# shift_clock_v2_0.net
KiCad netlist of a schematic drawn in EAGLE
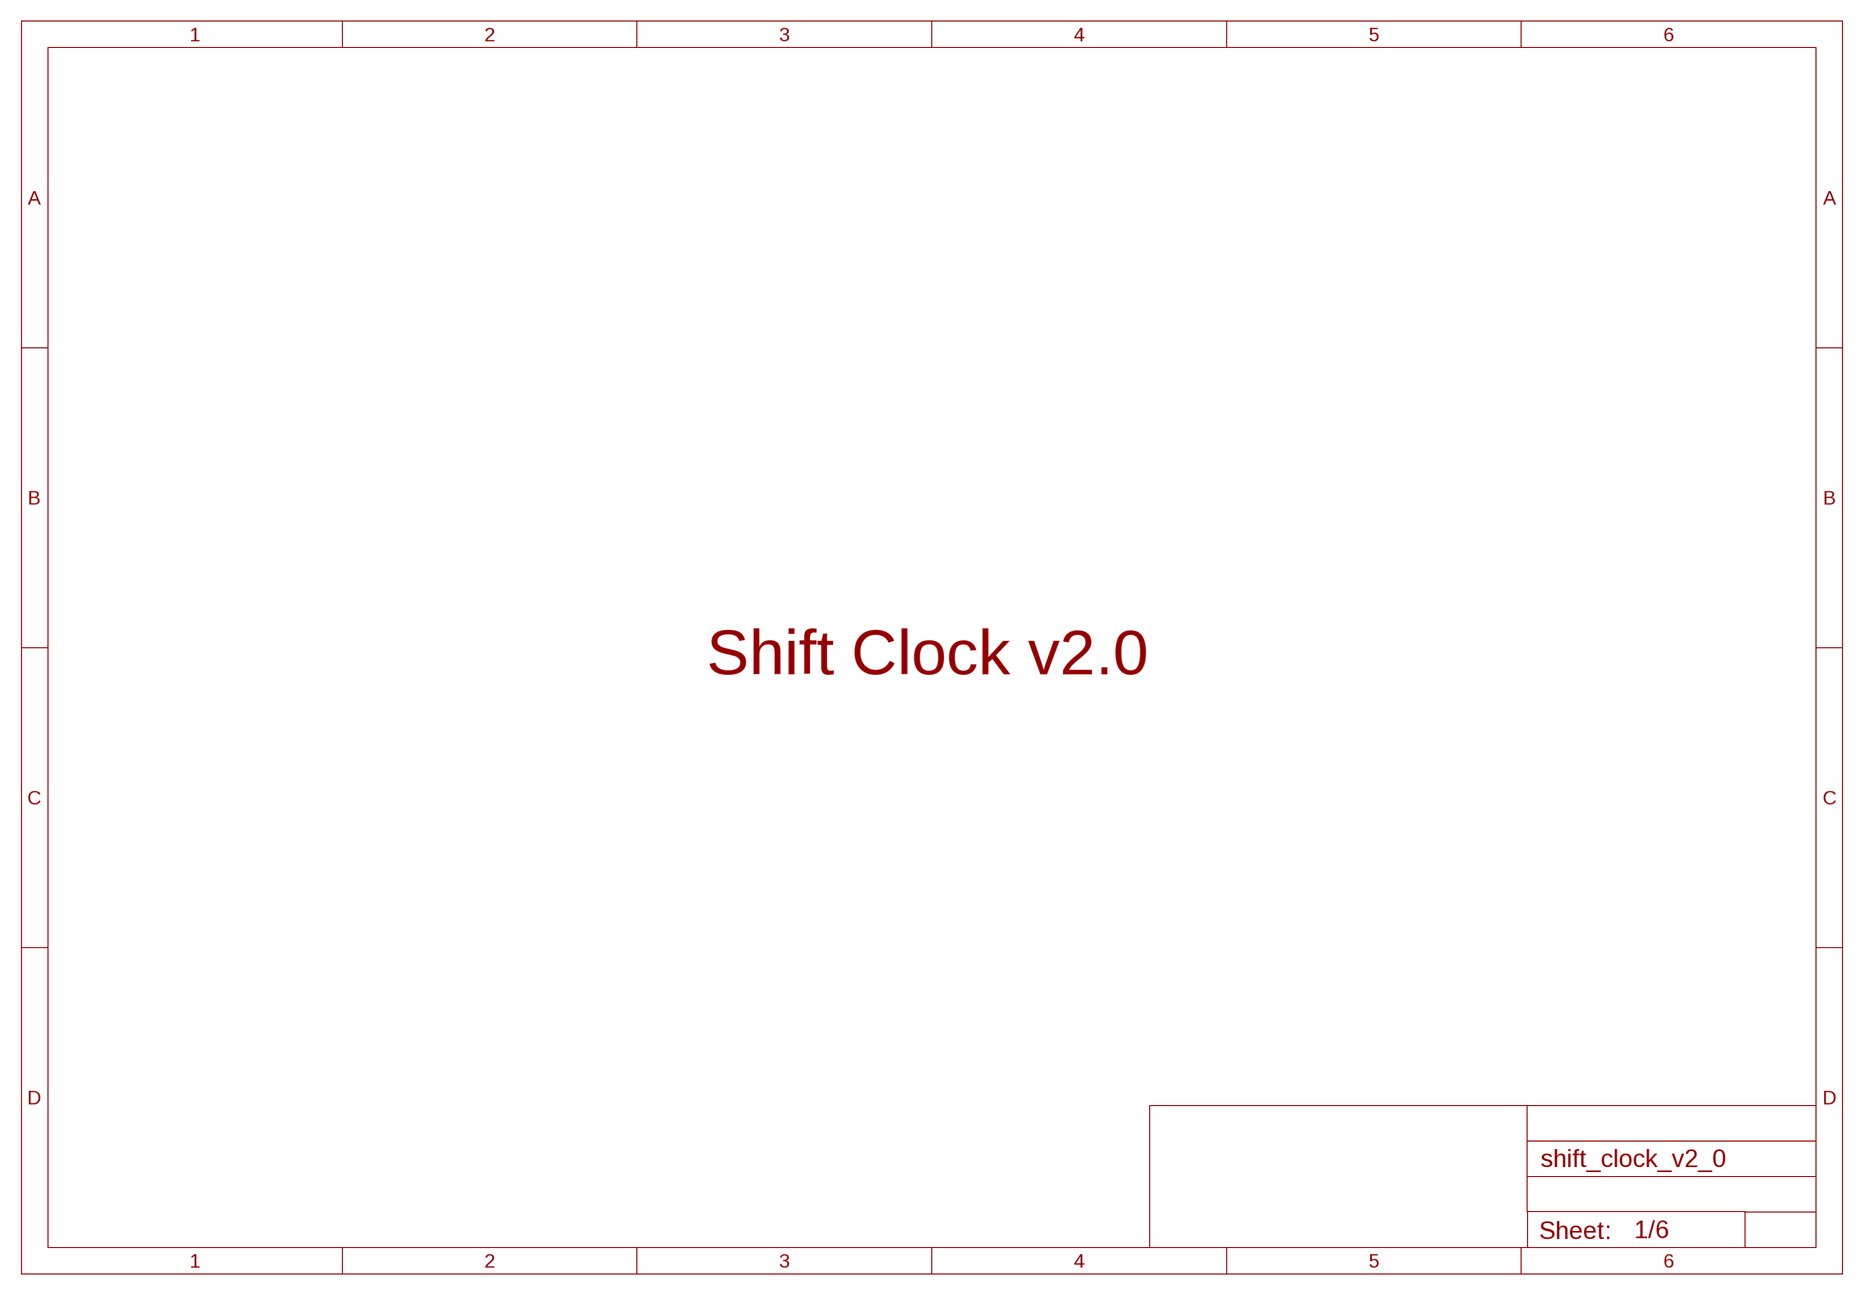
[diagram p0: schematic, sheet 1]
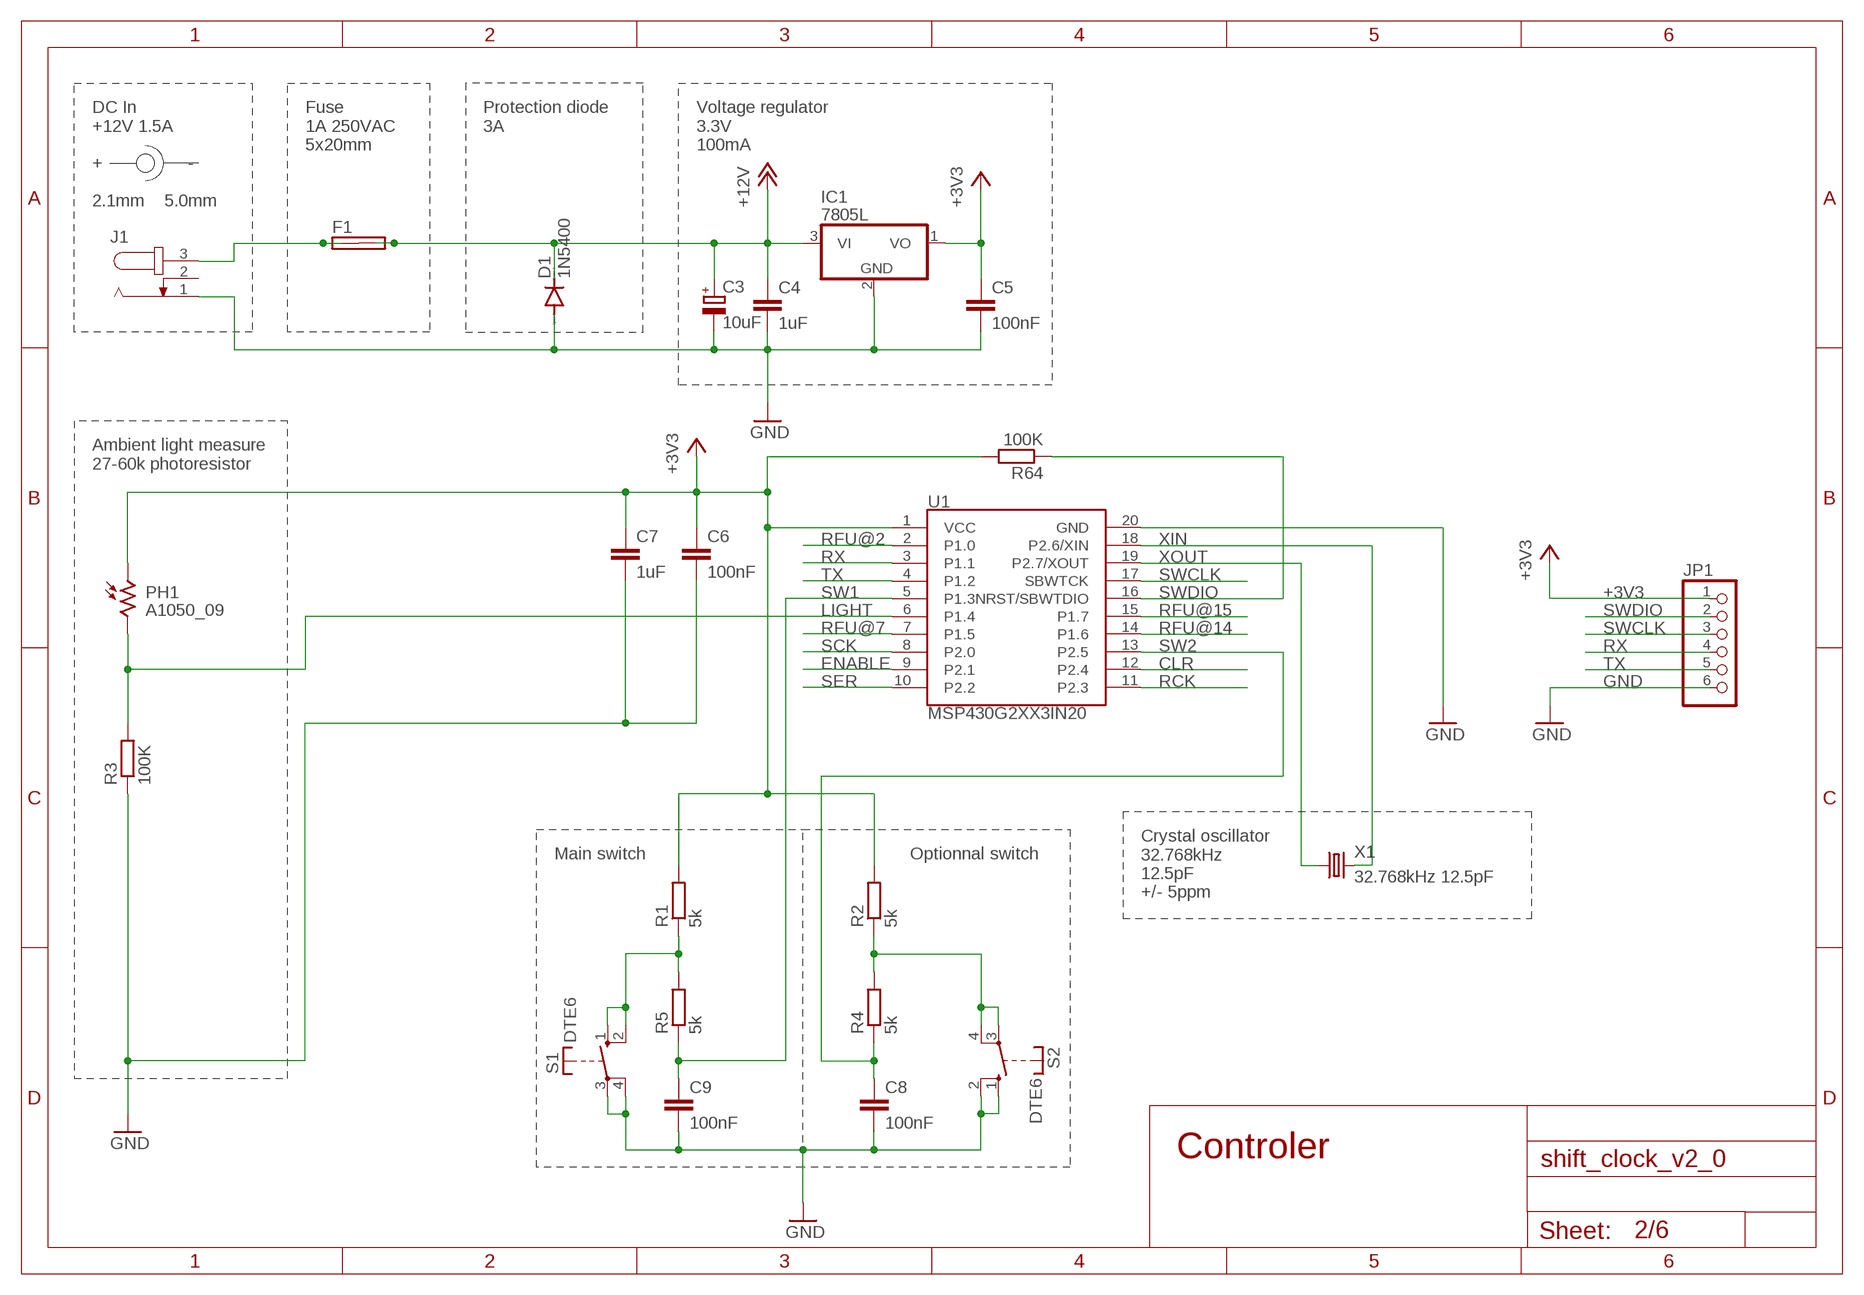
[diagram p1: schematic, sheet 2]
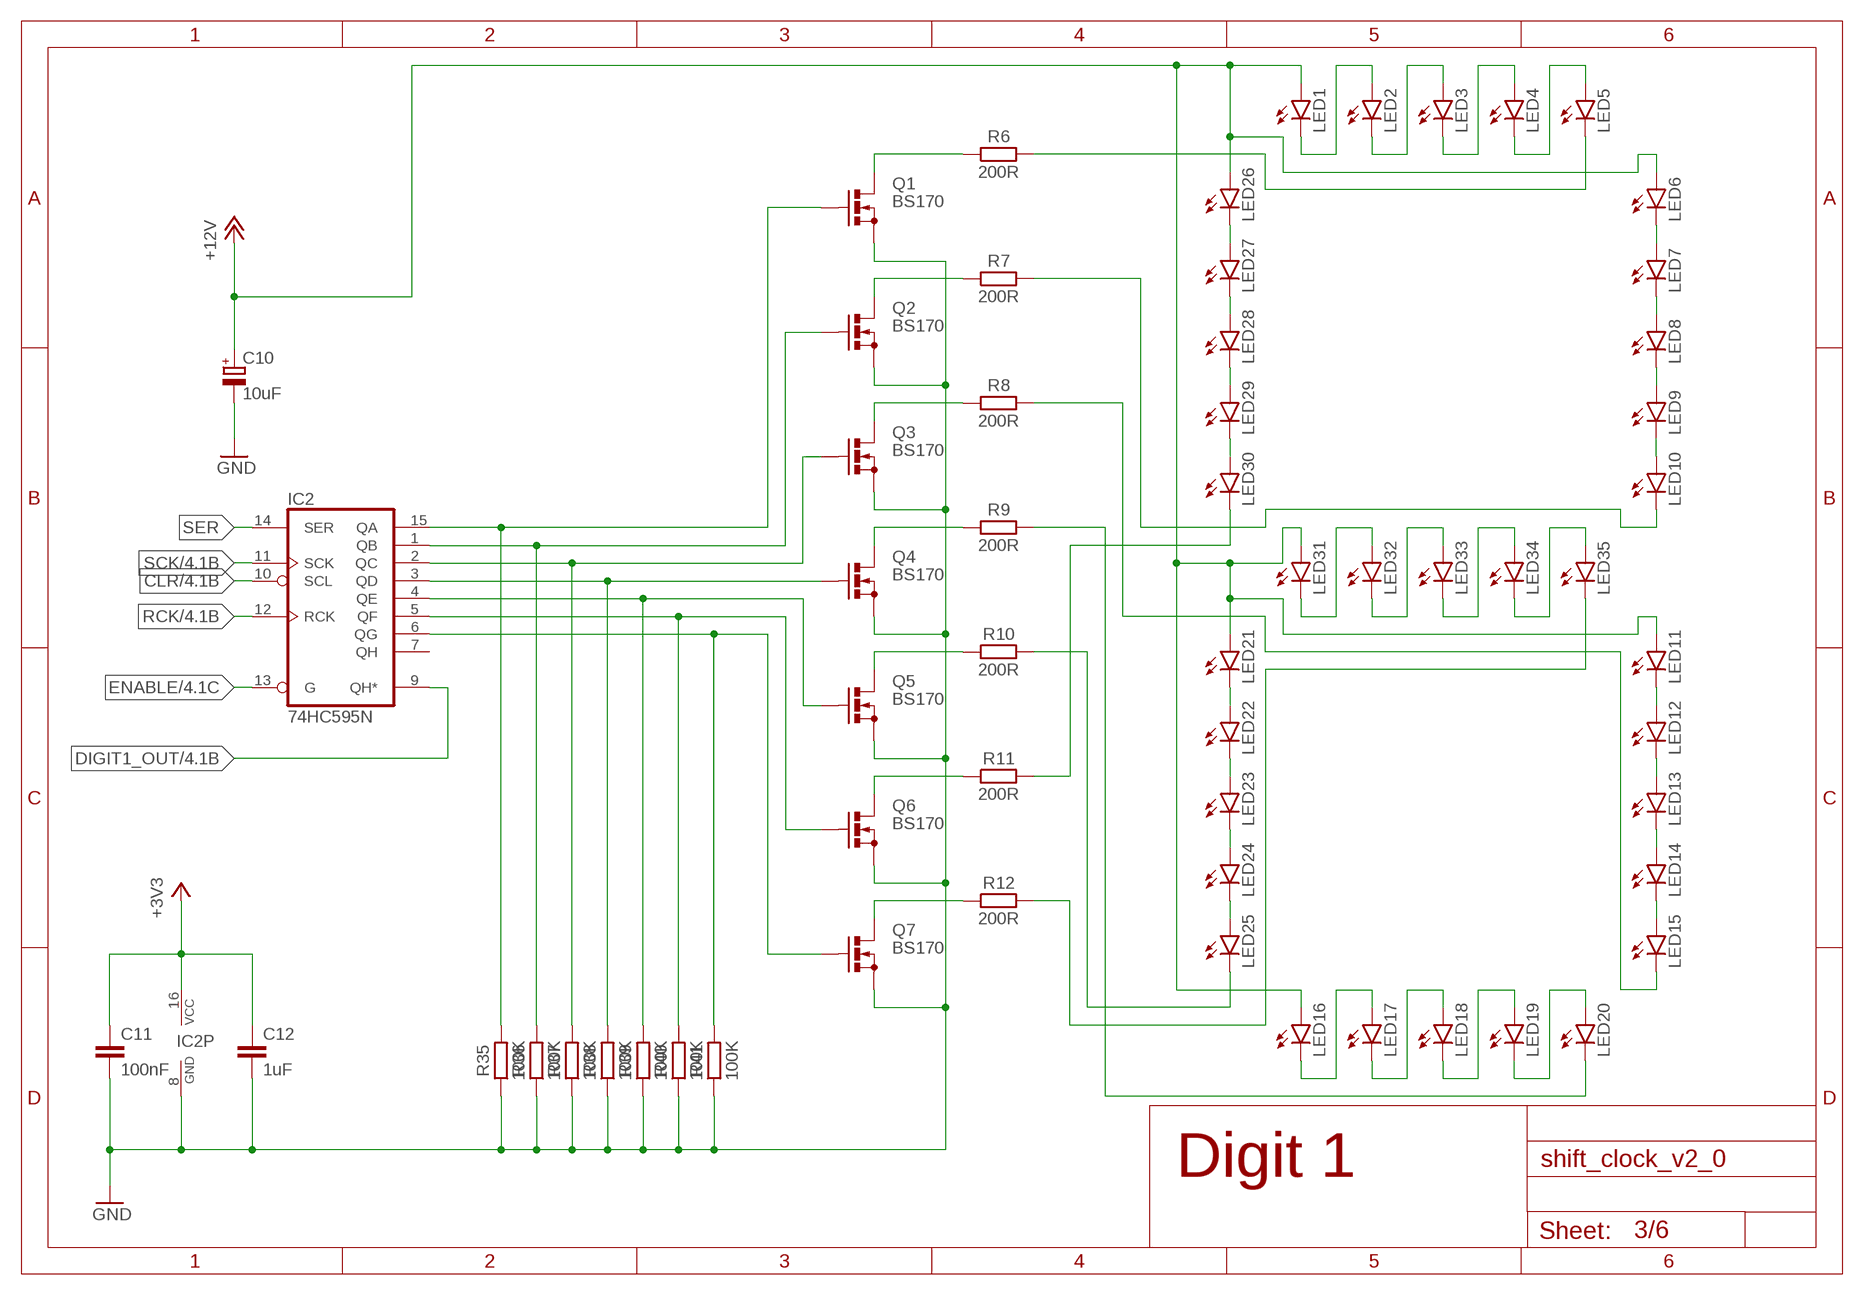
[diagram p2: schematic, sheet 3]
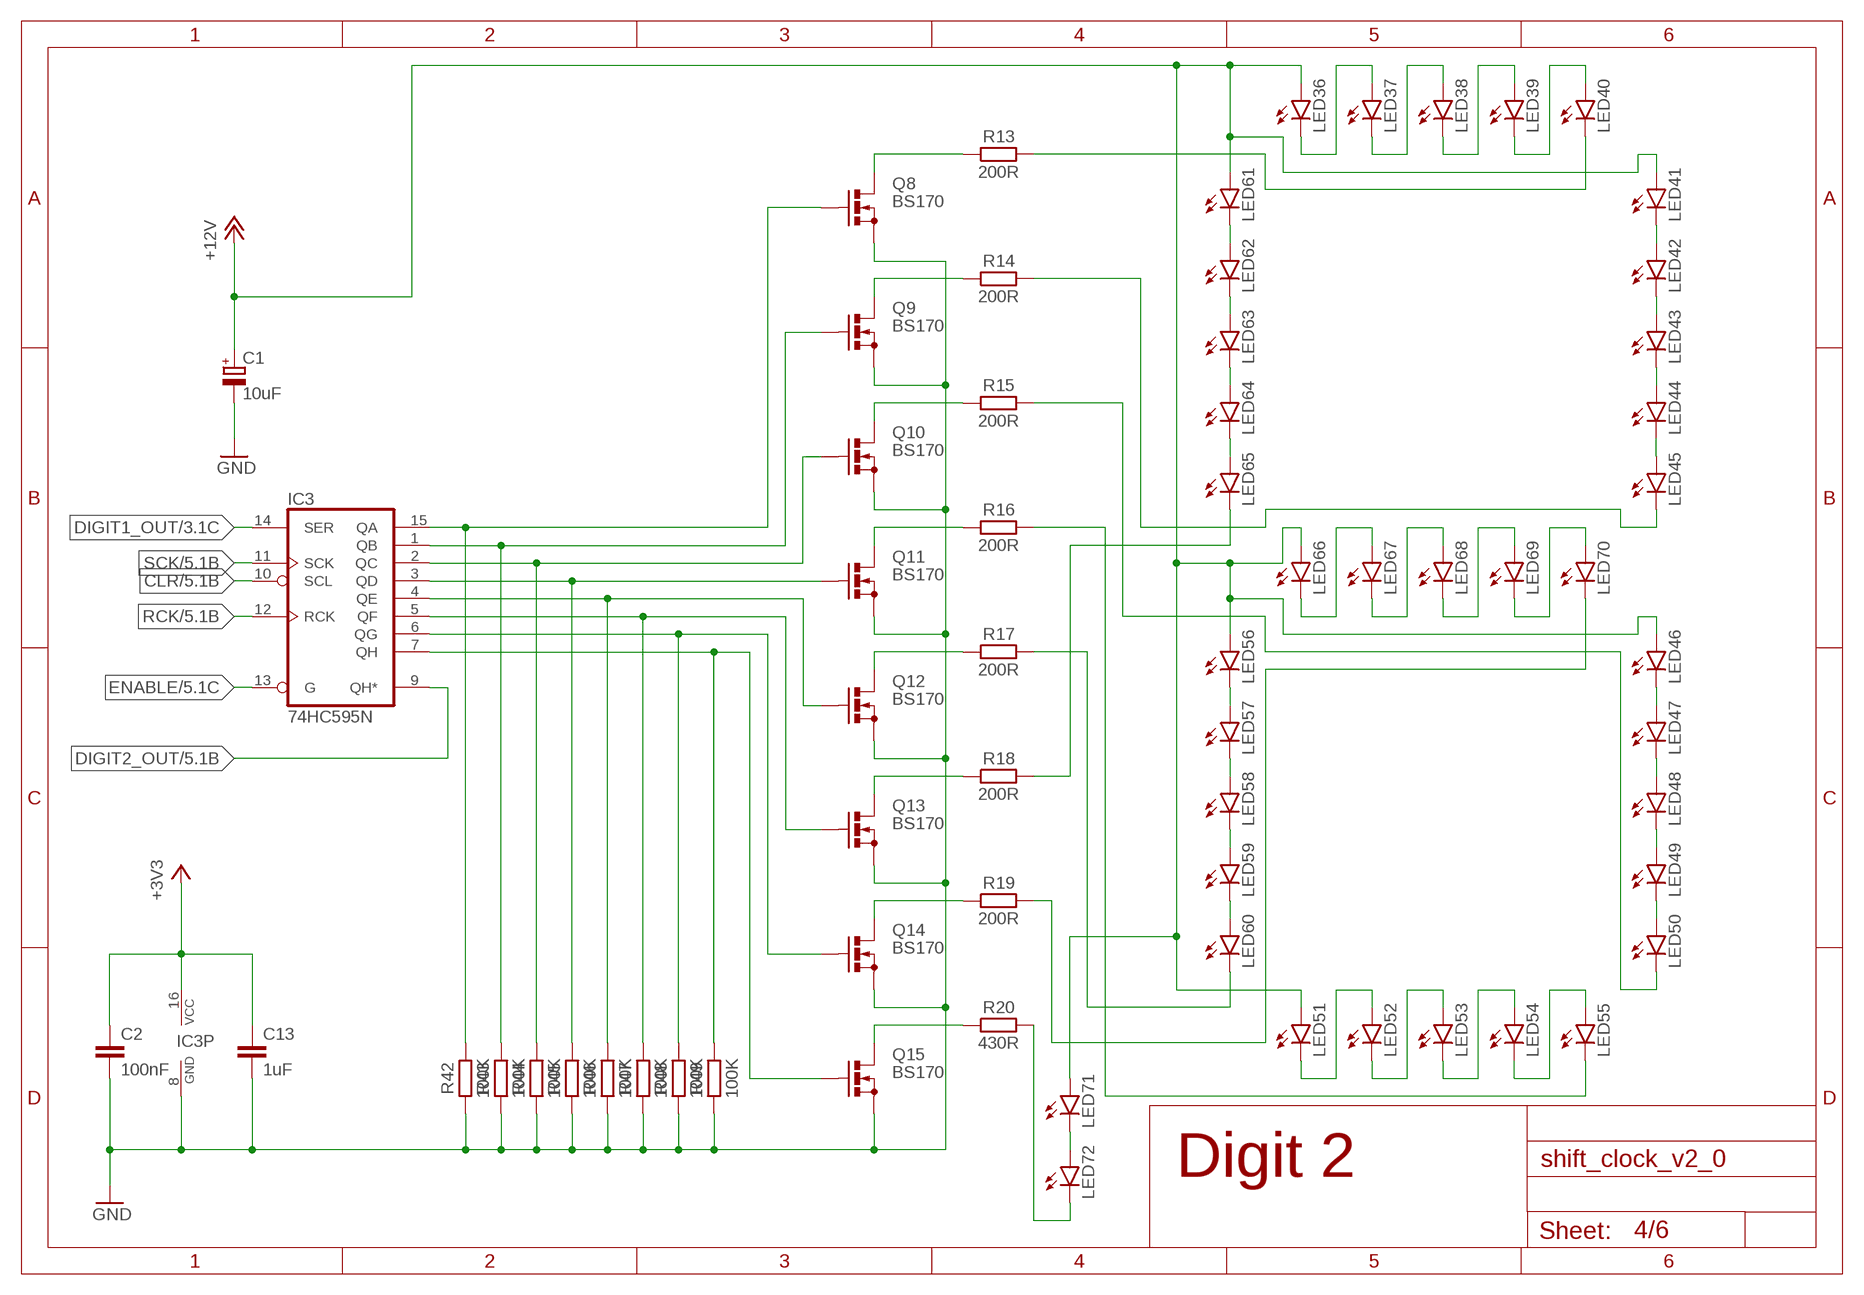
[diagram p3: schematic, sheet 4]
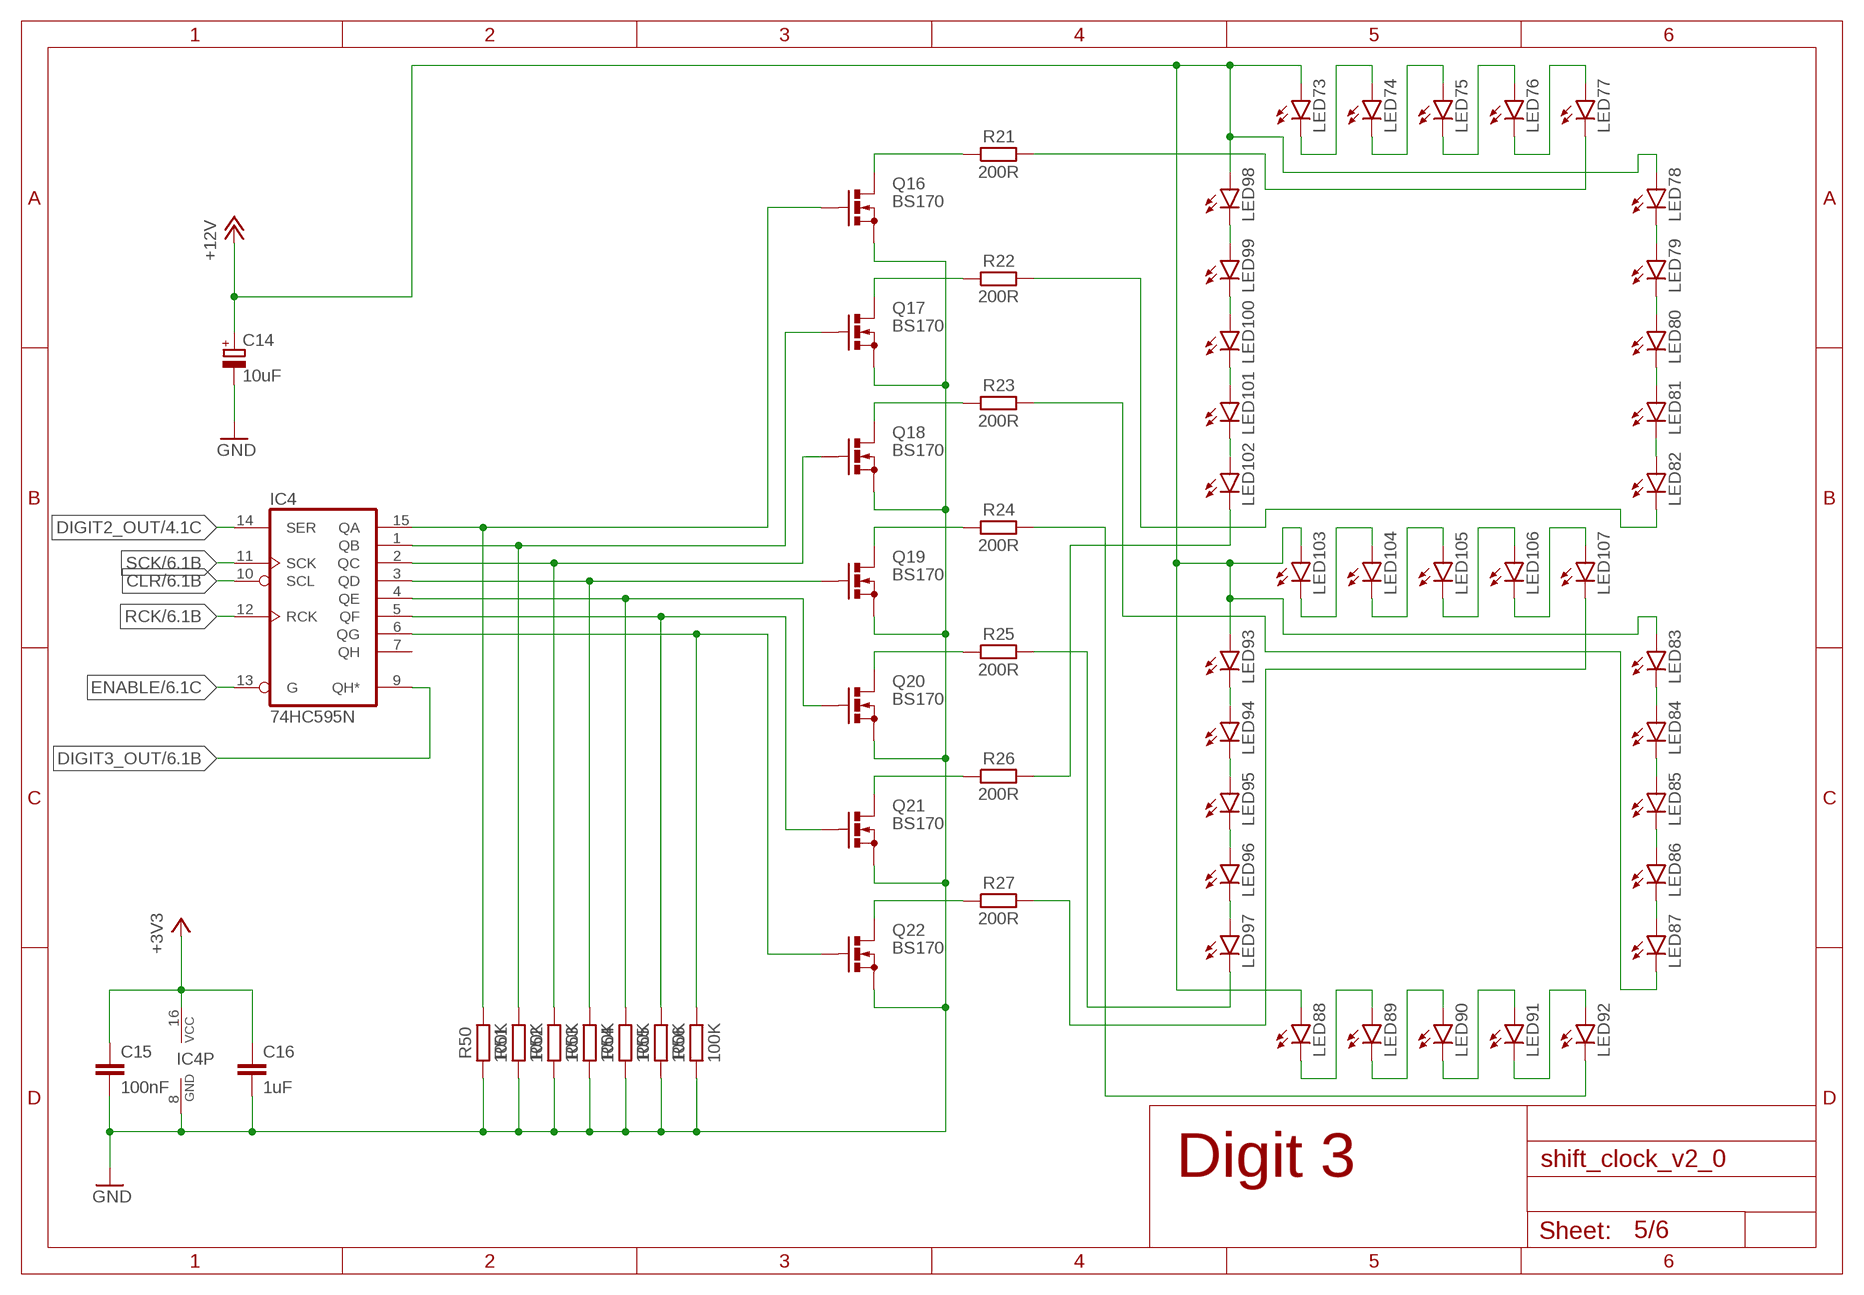
[diagram p4: schematic, sheet 5]
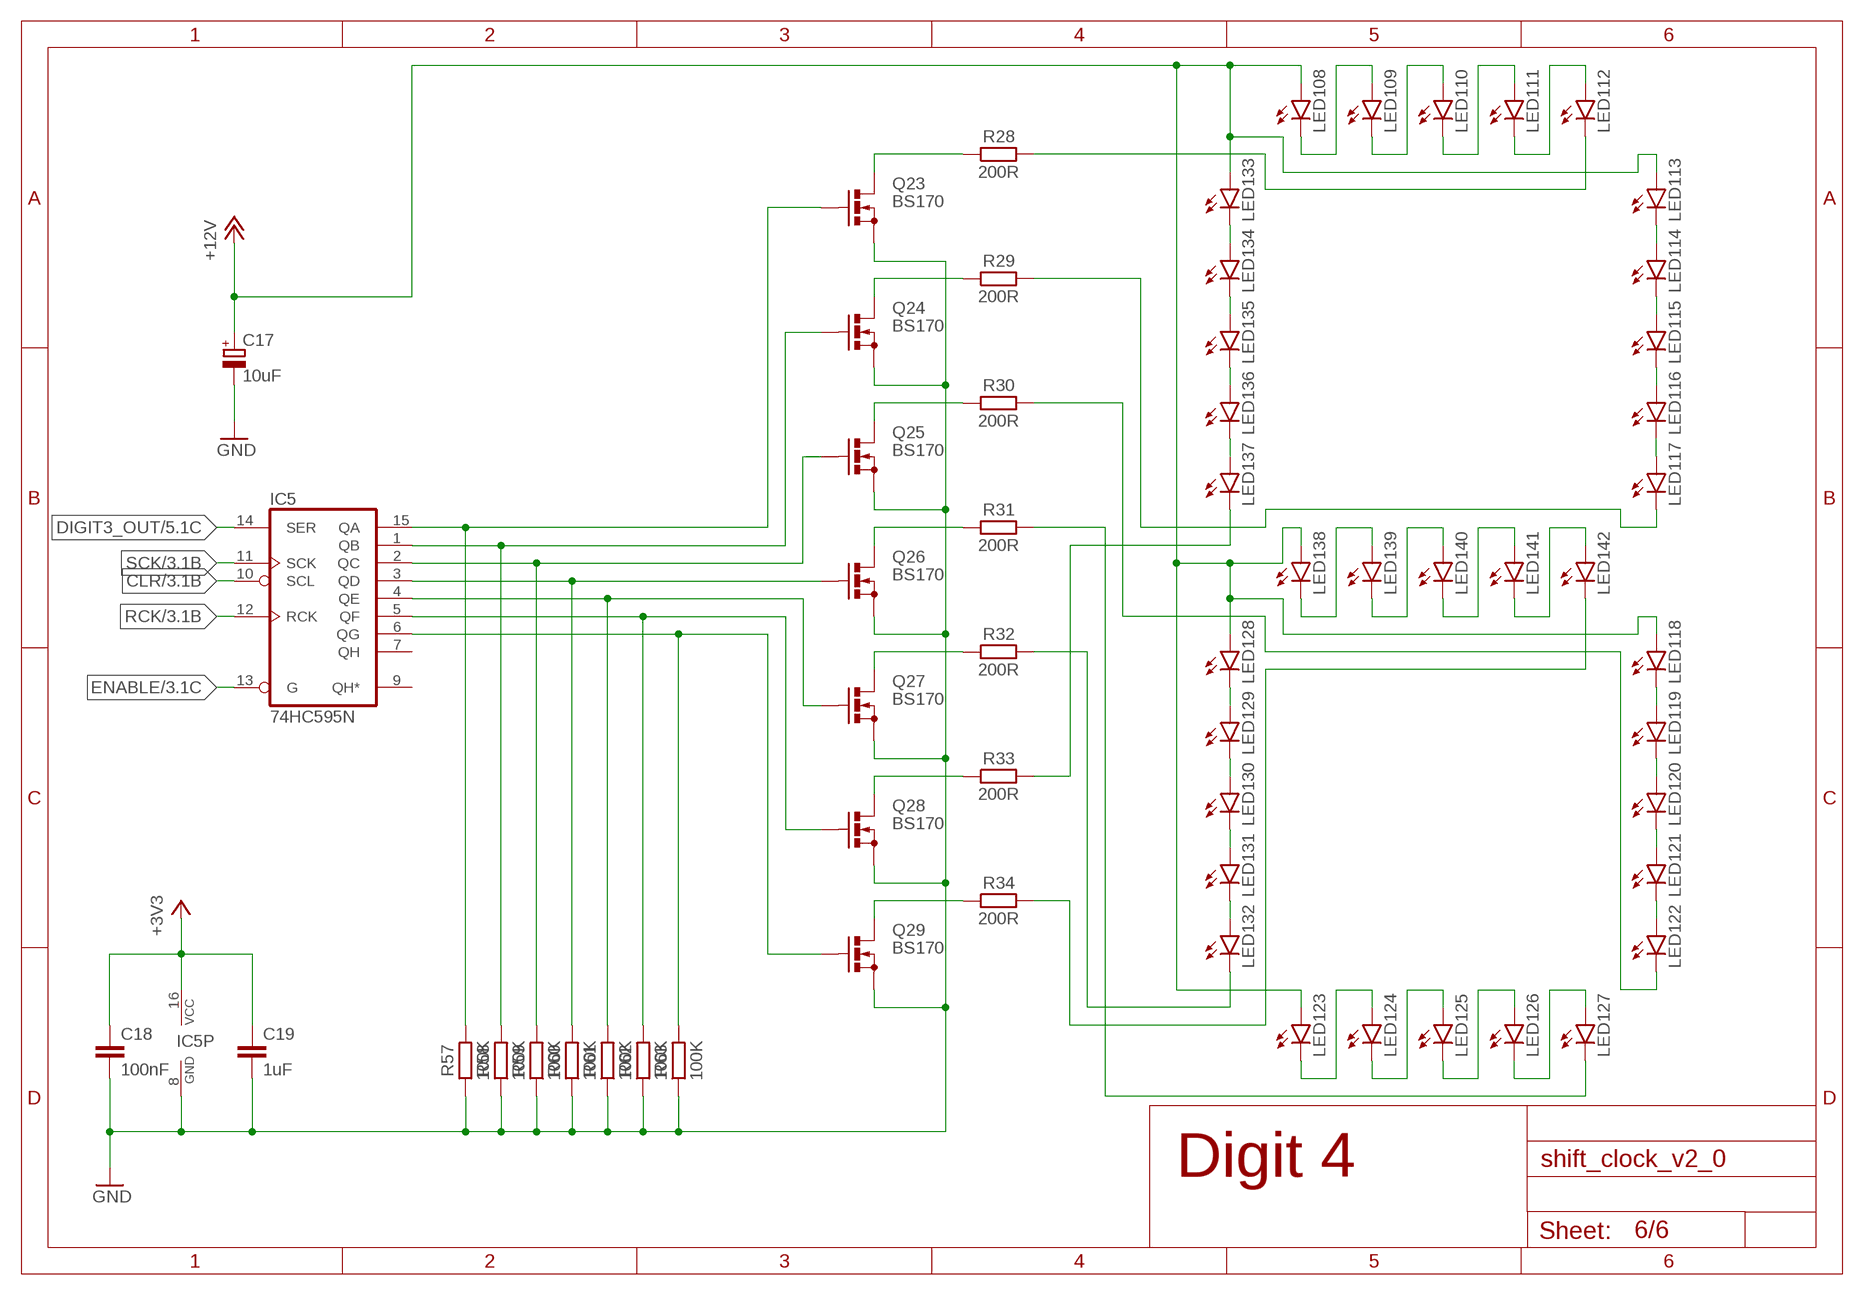
[diagram p5: schematic, sheet 6]

(export (version "E")
  (design (tool "Eeschema 10.0.6"))
  (components
    (comp (ref "C17")
      (value "10uF")
      (footprint "eagle-import:E2,5-6")
      (libsource (lib "eagle-import") (part "CPOL-EUE2.5-6"))
    )
    (comp (ref "C18")
      (value "100nF")
      (footprint "eagle-import:C050-024X044")
      (libsource (lib "eagle-import") (part "C-EU050-024X044"))
    )
    (comp (ref "C19")
      (value "1uF")
      (footprint "eagle-import:C050-024X044")
      (libsource (lib "eagle-import") (part "C-EU050-024X044"))
    )
    (comp (ref "IC5")
      (value "74HC595N")
      (footprint "eagle-import:DIL16")
      (libsource (lib "eagle-import") (part "74595NHC"))
    )
    (comp (ref "LED108")
      (value "LED25X70")
      (footprint "eagle-import:LED25X70")
      (libsource (lib "eagle-import") (part "LED25X70"))
    )
    (comp (ref "LED109")
      (value "LED25X70")
      (footprint "eagle-import:LED25X70")
      (libsource (lib "eagle-import") (part "LED25X70"))
    )
    (comp (ref "LED110")
      (value "LED25X70")
      (footprint "eagle-import:LED25X70")
      (libsource (lib "eagle-import") (part "LED25X70"))
    )
    (comp (ref "LED111")
      (value "LED25X70")
      (footprint "eagle-import:LED25X70")
      (libsource (lib "eagle-import") (part "LED25X70"))
    )
    (comp (ref "LED112")
      (value "LED25X70")
      (footprint "eagle-import:LED25X70")
      (libsource (lib "eagle-import") (part "LED25X70"))
    )
    (comp (ref "LED113")
      (value "LED25X70")
      (footprint "eagle-import:LED25X70")
      (libsource (lib "eagle-import") (part "LED25X70"))
    )
    (comp (ref "LED114")
      (value "LED25X70")
      (footprint "eagle-import:LED25X70")
      (libsource (lib "eagle-import") (part "LED25X70"))
    )
    (comp (ref "LED115")
      (value "LED25X70")
      (footprint "eagle-import:LED25X70")
      (libsource (lib "eagle-import") (part "LED25X70"))
    )
    (comp (ref "LED116")
      (value "LED25X70")
      (footprint "eagle-import:LED25X70")
      (libsource (lib "eagle-import") (part "LED25X70"))
    )
    (comp (ref "LED117")
      (value "LED25X70")
      (footprint "eagle-import:LED25X70")
      (libsource (lib "eagle-import") (part "LED25X70"))
    )
    (comp (ref "LED118")
      (value "LED25X70")
      (footprint "eagle-import:LED25X70")
      (libsource (lib "eagle-import") (part "LED25X70"))
    )
    (comp (ref "LED119")
      (value "LED25X70")
      (footprint "eagle-import:LED25X70")
      (libsource (lib "eagle-import") (part "LED25X70"))
    )
    (comp (ref "LED120")
      (value "LED25X70")
      (footprint "eagle-import:LED25X70")
      (libsource (lib "eagle-import") (part "LED25X70"))
    )
    (comp (ref "LED121")
      (value "LED25X70")
      (footprint "eagle-import:LED25X70")
      (libsource (lib "eagle-import") (part "LED25X70"))
    )
    (comp (ref "LED122")
      (value "LED25X70")
      (footprint "eagle-import:LED25X70")
      (libsource (lib "eagle-import") (part "LED25X70"))
    )
    (comp (ref "LED123")
      (value "LED25X70")
      (footprint "eagle-import:LED25X70")
      (libsource (lib "eagle-import") (part "LED25X70"))
    )
    (comp (ref "LED124")
      (value "LED25X70")
      (footprint "eagle-import:LED25X70")
      (libsource (lib "eagle-import") (part "LED25X70"))
    )
    (comp (ref "LED125")
      (value "LED25X70")
      (footprint "eagle-import:LED25X70")
      (libsource (lib "eagle-import") (part "LED25X70"))
    )
    (comp (ref "LED126")
      (value "LED25X70")
      (footprint "eagle-import:LED25X70")
      (libsource (lib "eagle-import") (part "LED25X70"))
    )
    (comp (ref "LED127")
      (value "LED25X70")
      (footprint "eagle-import:LED25X70")
      (libsource (lib "eagle-import") (part "LED25X70"))
    )
    (comp (ref "LED128")
      (value "LED25X70")
      (footprint "eagle-import:LED25X70")
      (libsource (lib "eagle-import") (part "LED25X70"))
    )
    (comp (ref "LED129")
      (value "LED25X70")
      (footprint "eagle-import:LED25X70")
      (libsource (lib "eagle-import") (part "LED25X70"))
    )
    (comp (ref "LED130")
      (value "LED25X70")
      (footprint "eagle-import:LED25X70")
      (libsource (lib "eagle-import") (part "LED25X70"))
    )
    (comp (ref "LED131")
      (value "LED25X70")
      (footprint "eagle-import:LED25X70")
      (libsource (lib "eagle-import") (part "LED25X70"))
    )
    (comp (ref "LED132")
      (value "LED25X70")
      (footprint "eagle-import:LED25X70")
      (libsource (lib "eagle-import") (part "LED25X70"))
    )
    (comp (ref "LED133")
      (value "LED25X70")
      (footprint "eagle-import:LED25X70")
      (libsource (lib "eagle-import") (part "LED25X70"))
    )
    (comp (ref "LED134")
      (value "LED25X70")
      (footprint "eagle-import:LED25X70")
      (libsource (lib "eagle-import") (part "LED25X70"))
    )
    (comp (ref "LED135")
      (value "LED25X70")
      (footprint "eagle-import:LED25X70")
      (libsource (lib "eagle-import") (part "LED25X70"))
    )
    (comp (ref "LED136")
      (value "LED25X70")
      (footprint "eagle-import:LED25X70")
      (libsource (lib "eagle-import") (part "LED25X70"))
    )
    (comp (ref "LED137")
      (value "LED25X70")
      (footprint "eagle-import:LED25X70")
      (libsource (lib "eagle-import") (part "LED25X70"))
    )
    (comp (ref "LED138")
      (value "LED25X70")
      (footprint "eagle-import:LED25X70")
      (libsource (lib "eagle-import") (part "LED25X70"))
    )
    (comp (ref "LED139")
      (value "LED25X70")
      (footprint "eagle-import:LED25X70")
      (libsource (lib "eagle-import") (part "LED25X70"))
    )
    (comp (ref "LED140")
      (value "LED25X70")
      (footprint "eagle-import:LED25X70")
      (libsource (lib "eagle-import") (part "LED25X70"))
    )
    (comp (ref "LED141")
      (value "LED25X70")
      (footprint "eagle-import:LED25X70")
      (libsource (lib "eagle-import") (part "LED25X70"))
    )
    (comp (ref "LED142")
      (value "LED25X70")
      (footprint "eagle-import:LED25X70")
      (libsource (lib "eagle-import") (part "LED25X70"))
    )
    (comp (ref "Q23")
      (value "BS170")
      (footprint "eagle-import:SOT54E")
      (libsource (lib "eagle-import") (part "BS170"))
    )
    (comp (ref "Q24")
      (value "BS170")
      (footprint "eagle-import:SOT54E")
      (libsource (lib "eagle-import") (part "BS170"))
    )
    (comp (ref "Q25")
      (value "BS170")
      (footprint "eagle-import:SOT54E")
      (libsource (lib "eagle-import") (part "BS170"))
    )
    (comp (ref "Q26")
      (value "BS170")
      (footprint "eagle-import:SOT54E")
      (libsource (lib "eagle-import") (part "BS170"))
    )
    (comp (ref "Q27")
      (value "BS170")
      (footprint "eagle-import:SOT54E")
      (libsource (lib "eagle-import") (part "BS170"))
    )
    (comp (ref "Q28")
      (value "BS170")
      (footprint "eagle-import:SOT54E")
      (libsource (lib "eagle-import") (part "BS170"))
    )
    (comp (ref "Q29")
      (value "BS170")
      (footprint "eagle-import:SOT54E")
      (libsource (lib "eagle-import") (part "BS170"))
    )
    (comp (ref "R28")
      (value "200R")
      (footprint "eagle-import:0204_7")
      (libsource (lib "eagle-import") (part "R-EU_0204/7"))
    )
    (comp (ref "R29")
      (value "200R")
      (footprint "eagle-import:0204_7")
      (libsource (lib "eagle-import") (part "R-EU_0204/7"))
    )
    (comp (ref "R30")
      (value "200R")
      (footprint "eagle-import:0204_7")
      (libsource (lib "eagle-import") (part "R-EU_0204/7"))
    )
    (comp (ref "R31")
      (value "200R")
      (footprint "eagle-import:0204_7")
      (libsource (lib "eagle-import") (part "R-EU_0204/7"))
    )
    (comp (ref "R32")
      (value "200R")
      (footprint "eagle-import:0204_7")
      (libsource (lib "eagle-import") (part "R-EU_0204/7"))
    )
    (comp (ref "R33")
      (value "200R")
      (footprint "eagle-import:0204_7")
      (libsource (lib "eagle-import") (part "R-EU_0204/7"))
    )
    (comp (ref "R34")
      (value "200R")
      (footprint "eagle-import:0204_7")
      (libsource (lib "eagle-import") (part "R-EU_0204/7"))
    )
    (comp (ref "R57")
      (value "100K")
      (footprint "eagle-import:0204_7")
      (libsource (lib "eagle-import") (part "R-EU_0204/7"))
    )
    (comp (ref "R58")
      (value "100K")
      (footprint "eagle-import:0204_7")
      (libsource (lib "eagle-import") (part "R-EU_0204/7"))
    )
    (comp (ref "R59")
      (value "100K")
      (footprint "eagle-import:0204_7")
      (libsource (lib "eagle-import") (part "R-EU_0204/7"))
    )
    (comp (ref "R60")
      (value "100K")
      (footprint "eagle-import:0204_7")
      (libsource (lib "eagle-import") (part "R-EU_0204/7"))
    )
    (comp (ref "R61")
      (value "100K")
      (footprint "eagle-import:0204_7")
      (libsource (lib "eagle-import") (part "R-EU_0204/7"))
    )
    (comp (ref "R62")
      (value "100K")
      (footprint "eagle-import:0204_7")
      (libsource (lib "eagle-import") (part "R-EU_0204/7"))
    )
    (comp (ref "R63")
      (value "100K")
      (footprint "eagle-import:0204_7")
      (libsource (lib "eagle-import") (part "R-EU_0204/7"))
    )
    (comp (ref "C1")
      (value "10uF")
      (footprint "eagle-import:E2,5-6")
      (libsource (lib "eagle-import") (part "CPOL-EUE2.5-6"))
    )
    (comp (ref "C2")
      (value "100nF")
      (footprint "eagle-import:C050-024X044")
      (libsource (lib "eagle-import") (part "C-EU050-024X044"))
    )
    (comp (ref "C13")
      (value "1uF")
      (footprint "eagle-import:C050-024X044")
      (libsource (lib "eagle-import") (part "C-EU050-024X044"))
    )
    (comp (ref "IC3")
      (value "74HC595N")
      (footprint "eagle-import:DIL16")
      (libsource (lib "eagle-import") (part "74595NHC"))
    )
    (comp (ref "LED36")
      (value "LED25X70")
      (footprint "eagle-import:LED25X70")
      (libsource (lib "eagle-import") (part "LED25X70"))
    )
    (comp (ref "LED37")
      (value "LED25X70")
      (footprint "eagle-import:LED25X70")
      (libsource (lib "eagle-import") (part "LED25X70"))
    )
    (comp (ref "LED38")
      (value "LED25X70")
      (footprint "eagle-import:LED25X70")
      (libsource (lib "eagle-import") (part "LED25X70"))
    )
    (comp (ref "LED39")
      (value "LED25X70")
      (footprint "eagle-import:LED25X70")
      (libsource (lib "eagle-import") (part "LED25X70"))
    )
    (comp (ref "LED40")
      (value "LED25X70")
      (footprint "eagle-import:LED25X70")
      (libsource (lib "eagle-import") (part "LED25X70"))
    )
    (comp (ref "LED41")
      (value "LED25X70")
      (footprint "eagle-import:LED25X70")
      (libsource (lib "eagle-import") (part "LED25X70"))
    )
    (comp (ref "LED42")
      (value "LED25X70")
      (footprint "eagle-import:LED25X70")
      (libsource (lib "eagle-import") (part "LED25X70"))
    )
    (comp (ref "LED43")
      (value "LED25X70")
      (footprint "eagle-import:LED25X70")
      (libsource (lib "eagle-import") (part "LED25X70"))
    )
    (comp (ref "LED44")
      (value "LED25X70")
      (footprint "eagle-import:LED25X70")
      (libsource (lib "eagle-import") (part "LED25X70"))
    )
    (comp (ref "LED45")
      (value "LED25X70")
      (footprint "eagle-import:LED25X70")
      (libsource (lib "eagle-import") (part "LED25X70"))
    )
    (comp (ref "LED46")
      (value "LED25X70")
      (footprint "eagle-import:LED25X70")
      (libsource (lib "eagle-import") (part "LED25X70"))
    )
    (comp (ref "LED47")
      (value "LED25X70")
      (footprint "eagle-import:LED25X70")
      (libsource (lib "eagle-import") (part "LED25X70"))
    )
    (comp (ref "LED48")
      (value "LED25X70")
      (footprint "eagle-import:LED25X70")
      (libsource (lib "eagle-import") (part "LED25X70"))
    )
    (comp (ref "LED49")
      (value "LED25X70")
      (footprint "eagle-import:LED25X70")
      (libsource (lib "eagle-import") (part "LED25X70"))
    )
    (comp (ref "LED50")
      (value "LED25X70")
      (footprint "eagle-import:LED25X70")
      (libsource (lib "eagle-import") (part "LED25X70"))
    )
    (comp (ref "LED51")
      (value "LED25X70")
      (footprint "eagle-import:LED25X70")
      (libsource (lib "eagle-import") (part "LED25X70"))
    )
    (comp (ref "LED52")
      (value "LED25X70")
      (footprint "eagle-import:LED25X70")
      (libsource (lib "eagle-import") (part "LED25X70"))
    )
    (comp (ref "LED53")
      (value "LED25X70")
      (footprint "eagle-import:LED25X70")
      (libsource (lib "eagle-import") (part "LED25X70"))
    )
    (comp (ref "LED54")
      (value "LED25X70")
      (footprint "eagle-import:LED25X70")
      (libsource (lib "eagle-import") (part "LED25X70"))
    )
    (comp (ref "LED55")
      (value "LED25X70")
      (footprint "eagle-import:LED25X70")
      (libsource (lib "eagle-import") (part "LED25X70"))
    )
    (comp (ref "LED56")
      (value "LED25X70")
      (footprint "eagle-import:LED25X70")
      (libsource (lib "eagle-import") (part "LED25X70"))
    )
    (comp (ref "LED57")
      (value "LED25X70")
      (footprint "eagle-import:LED25X70")
      (libsource (lib "eagle-import") (part "LED25X70"))
    )
    (comp (ref "LED58")
      (value "LED25X70")
      (footprint "eagle-import:LED25X70")
      (libsource (lib "eagle-import") (part "LED25X70"))
    )
    (comp (ref "LED59")
      (value "LED25X70")
      (footprint "eagle-import:LED25X70")
      (libsource (lib "eagle-import") (part "LED25X70"))
    )
    (comp (ref "LED60")
      (value "LED25X70")
      (footprint "eagle-import:LED25X70")
      (libsource (lib "eagle-import") (part "LED25X70"))
    )
    (comp (ref "LED61")
      (value "LED25X70")
      (footprint "eagle-import:LED25X70")
      (libsource (lib "eagle-import") (part "LED25X70"))
    )
    (comp (ref "LED62")
      (value "LED25X70")
      (footprint "eagle-import:LED25X70")
      (libsource (lib "eagle-import") (part "LED25X70"))
    )
    (comp (ref "LED63")
      (value "LED25X70")
      (footprint "eagle-import:LED25X70")
      (libsource (lib "eagle-import") (part "LED25X70"))
    )
    (comp (ref "LED64")
      (value "LED25X70")
      (footprint "eagle-import:LED25X70")
      (libsource (lib "eagle-import") (part "LED25X70"))
    )
    (comp (ref "LED65")
      (value "LED25X70")
      (footprint "eagle-import:LED25X70")
      (libsource (lib "eagle-import") (part "LED25X70"))
    )
    (comp (ref "LED66")
      (value "LED25X70")
      (footprint "eagle-import:LED25X70")
      (libsource (lib "eagle-import") (part "LED25X70"))
    )
    (comp (ref "LED67")
      (value "LED25X70")
      (footprint "eagle-import:LED25X70")
      (libsource (lib "eagle-import") (part "LED25X70"))
    )
    (comp (ref "LED68")
      (value "LED25X70")
      (footprint "eagle-import:LED25X70")
      (libsource (lib "eagle-import") (part "LED25X70"))
    )
    (comp (ref "LED69")
      (value "LED25X70")
      (footprint "eagle-import:LED25X70")
      (libsource (lib "eagle-import") (part "LED25X70"))
    )
    (comp (ref "LED70")
      (value "LED25X70")
      (footprint "eagle-import:LED25X70")
      (libsource (lib "eagle-import") (part "LED25X70"))
    )
    (comp (ref "LED71")
      (value "LED25X70")
      (footprint "eagle-import:LED25X70")
      (libsource (lib "eagle-import") (part "LED25X70"))
    )
    (comp (ref "LED72")
      (value "LED25X70")
      (footprint "eagle-import:LED25X70")
      (libsource (lib "eagle-import") (part "LED25X70"))
    )
    (comp (ref "Q8")
      (value "BS170")
      (footprint "eagle-import:SOT54E")
      (libsource (lib "eagle-import") (part "BS170"))
    )
    (comp (ref "Q9")
      (value "BS170")
      (footprint "eagle-import:SOT54E")
      (libsource (lib "eagle-import") (part "BS170"))
    )
    (comp (ref "Q10")
      (value "BS170")
      (footprint "eagle-import:SOT54E")
      (libsource (lib "eagle-import") (part "BS170"))
    )
    (comp (ref "Q11")
      (value "BS170")
      (footprint "eagle-import:SOT54E")
      (libsource (lib "eagle-import") (part "BS170"))
    )
    (comp (ref "Q12")
      (value "BS170")
      (footprint "eagle-import:SOT54E")
      (libsource (lib "eagle-import") (part "BS170"))
    )
    (comp (ref "Q13")
      (value "BS170")
      (footprint "eagle-import:SOT54E")
      (libsource (lib "eagle-import") (part "BS170"))
    )
    (comp (ref "Q14")
      (value "BS170")
      (footprint "eagle-import:SOT54E")
      (libsource (lib "eagle-import") (part "BS170"))
    )
    (comp (ref "Q15")
      (value "BS170")
      (footprint "eagle-import:SOT54E")
      (libsource (lib "eagle-import") (part "BS170"))
    )
    (comp (ref "R13")
      (value "200R")
      (footprint "eagle-import:0204_7")
      (libsource (lib "eagle-import") (part "R-EU_0204/7"))
    )
    (comp (ref "R14")
      (value "200R")
      (footprint "eagle-import:0204_7")
      (libsource (lib "eagle-import") (part "R-EU_0204/7"))
    )
    (comp (ref "R15")
      (value "200R")
      (footprint "eagle-import:0204_7")
      (libsource (lib "eagle-import") (part "R-EU_0204/7"))
    )
    (comp (ref "R16")
      (value "200R")
      (footprint "eagle-import:0204_7")
      (libsource (lib "eagle-import") (part "R-EU_0204/7"))
    )
    (comp (ref "R17")
      (value "200R")
      (footprint "eagle-import:0204_7")
      (libsource (lib "eagle-import") (part "R-EU_0204/7"))
    )
    (comp (ref "R18")
      (value "200R")
      (footprint "eagle-import:0204_7")
      (libsource (lib "eagle-import") (part "R-EU_0204/7"))
    )
    (comp (ref "R19")
      (value "200R")
      (footprint "eagle-import:0204_7")
      (libsource (lib "eagle-import") (part "R-EU_0204/7"))
    )
    (comp (ref "R20")
      (value "430R")
      (footprint "eagle-import:0204_7")
      (libsource (lib "eagle-import") (part "R-EU_0204/7"))
    )
    (comp (ref "R42")
      (value "100K")
      (footprint "eagle-import:0204_7")
      (libsource (lib "eagle-import") (part "R-EU_0204/7"))
    )
    (comp (ref "R43")
      (value "100K")
      (footprint "eagle-import:0204_7")
      (libsource (lib "eagle-import") (part "R-EU_0204/7"))
    )
    (comp (ref "R44")
      (value "100K")
      (footprint "eagle-import:0204_7")
      (libsource (lib "eagle-import") (part "R-EU_0204/7"))
    )
    (comp (ref "R45")
      (value "100K")
      (footprint "eagle-import:0204_7")
      (libsource (lib "eagle-import") (part "R-EU_0204/7"))
    )
    (comp (ref "R46")
      (value "100K")
      (footprint "eagle-import:0204_7")
      (libsource (lib "eagle-import") (part "R-EU_0204/7"))
    )
    (comp (ref "R47")
      (value "100K")
      (footprint "eagle-import:0204_7")
      (libsource (lib "eagle-import") (part "R-EU_0204/7"))
    )
    (comp (ref "R48")
      (value "100K")
      (footprint "eagle-import:0204_7")
      (libsource (lib "eagle-import") (part "R-EU_0204/7"))
    )
    (comp (ref "R49")
      (value "100K")
      (footprint "eagle-import:0204_7")
      (libsource (lib "eagle-import") (part "R-EU_0204/7"))
    )
    (comp (ref "C10")
      (value "10uF")
      (footprint "eagle-import:E2,5-6")
      (libsource (lib "eagle-import") (part "CPOL-EUE2.5-6"))
    )
    (comp (ref "C11")
      (value "100nF")
      (footprint "eagle-import:C050-024X044")
      (libsource (lib "eagle-import") (part "C-EU050-024X044"))
    )
    (comp (ref "C12")
      (value "1uF")
      (footprint "eagle-import:C050-024X044")
      (libsource (lib "eagle-import") (part "C-EU050-024X044"))
    )
    (comp (ref "IC2")
      (value "74HC595N")
      (footprint "eagle-import:DIL16")
      (libsource (lib "eagle-import") (part "74595NHC"))
    )
    (comp (ref "LED1")
      (value "LED25X70")
      (footprint "eagle-import:LED25X70")
      (libsource (lib "eagle-import") (part "LED25X70"))
    )
    (comp (ref "LED2")
      (value "LED25X70")
      (footprint "eagle-import:LED25X70")
      (libsource (lib "eagle-import") (part "LED25X70"))
    )
    (comp (ref "LED3")
      (value "LED25X70")
      (footprint "eagle-import:LED25X70")
      (libsource (lib "eagle-import") (part "LED25X70"))
    )
    (comp (ref "LED4")
      (value "LED25X70")
      (footprint "eagle-import:LED25X70")
      (libsource (lib "eagle-import") (part "LED25X70"))
    )
    (comp (ref "LED5")
      (value "LED25X70")
      (footprint "eagle-import:LED25X70")
      (libsource (lib "eagle-import") (part "LED25X70"))
    )
    (comp (ref "LED6")
      (value "LED25X70")
      (footprint "eagle-import:LED25X70")
      (libsource (lib "eagle-import") (part "LED25X70"))
    )
    (comp (ref "LED7")
      (value "LED25X70")
      (footprint "eagle-import:LED25X70")
      (libsource (lib "eagle-import") (part "LED25X70"))
    )
    (comp (ref "LED8")
      (value "LED25X70")
      (footprint "eagle-import:LED25X70")
      (libsource (lib "eagle-import") (part "LED25X70"))
    )
    (comp (ref "LED9")
      (value "LED25X70")
      (footprint "eagle-import:LED25X70")
      (libsource (lib "eagle-import") (part "LED25X70"))
    )
    (comp (ref "LED10")
      (value "LED25X70")
      (footprint "eagle-import:LED25X70")
      (libsource (lib "eagle-import") (part "LED25X70"))
    )
    (comp (ref "LED11")
      (value "LED25X70")
      (footprint "eagle-import:LED25X70")
      (libsource (lib "eagle-import") (part "LED25X70"))
    )
    (comp (ref "LED12")
      (value "LED25X70")
      (footprint "eagle-import:LED25X70")
      (libsource (lib "eagle-import") (part "LED25X70"))
    )
    (comp (ref "LED13")
      (value "LED25X70")
      (footprint "eagle-import:LED25X70")
      (libsource (lib "eagle-import") (part "LED25X70"))
    )
    (comp (ref "LED14")
      (value "LED25X70")
      (footprint "eagle-import:LED25X70")
      (libsource (lib "eagle-import") (part "LED25X70"))
    )
    (comp (ref "LED15")
      (value "LED25X70")
      (footprint "eagle-import:LED25X70")
      (libsource (lib "eagle-import") (part "LED25X70"))
    )
    (comp (ref "LED16")
      (value "LED25X70")
      (footprint "eagle-import:LED25X70")
      (libsource (lib "eagle-import") (part "LED25X70"))
    )
    (comp (ref "LED17")
      (value "LED25X70")
      (footprint "eagle-import:LED25X70")
      (libsource (lib "eagle-import") (part "LED25X70"))
    )
    (comp (ref "LED18")
      (value "LED25X70")
      (footprint "eagle-import:LED25X70")
      (libsource (lib "eagle-import") (part "LED25X70"))
    )
    (comp (ref "LED19")
      (value "LED25X70")
      (footprint "eagle-import:LED25X70")
      (libsource (lib "eagle-import") (part "LED25X70"))
    )
    (comp (ref "LED20")
      (value "LED25X70")
      (footprint "eagle-import:LED25X70")
      (libsource (lib "eagle-import") (part "LED25X70"))
    )
    (comp (ref "LED21")
      (value "LED25X70")
      (footprint "eagle-import:LED25X70")
      (libsource (lib "eagle-import") (part "LED25X70"))
    )
    (comp (ref "LED22")
      (value "LED25X70")
      (footprint "eagle-import:LED25X70")
      (libsource (lib "eagle-import") (part "LED25X70"))
    )
    (comp (ref "LED23")
      (value "LED25X70")
      (footprint "eagle-import:LED25X70")
      (libsource (lib "eagle-import") (part "LED25X70"))
    )
    (comp (ref "LED24")
      (value "LED25X70")
      (footprint "eagle-import:LED25X70")
      (libsource (lib "eagle-import") (part "LED25X70"))
    )
    (comp (ref "LED25")
      (value "LED25X70")
      (footprint "eagle-import:LED25X70")
      (libsource (lib "eagle-import") (part "LED25X70"))
    )
    (comp (ref "LED26")
      (value "LED25X70")
      (footprint "eagle-import:LED25X70")
      (libsource (lib "eagle-import") (part "LED25X70"))
    )
    (comp (ref "LED27")
      (value "LED25X70")
      (footprint "eagle-import:LED25X70")
      (libsource (lib "eagle-import") (part "LED25X70"))
    )
    (comp (ref "LED28")
      (value "LED25X70")
      (footprint "eagle-import:LED25X70")
      (libsource (lib "eagle-import") (part "LED25X70"))
    )
    (comp (ref "LED29")
      (value "LED25X70")
      (footprint "eagle-import:LED25X70")
      (libsource (lib "eagle-import") (part "LED25X70"))
    )
    (comp (ref "LED30")
      (value "LED25X70")
      (footprint "eagle-import:LED25X70")
      (libsource (lib "eagle-import") (part "LED25X70"))
    )
    (comp (ref "LED31")
      (value "LED25X70")
      (footprint "eagle-import:LED25X70")
      (libsource (lib "eagle-import") (part "LED25X70"))
    )
    (comp (ref "LED32")
      (value "LED25X70")
      (footprint "eagle-import:LED25X70")
      (libsource (lib "eagle-import") (part "LED25X70"))
    )
    (comp (ref "LED33")
      (value "LED25X70")
      (footprint "eagle-import:LED25X70")
      (libsource (lib "eagle-import") (part "LED25X70"))
    )
    (comp (ref "LED34")
      (value "LED25X70")
      (footprint "eagle-import:LED25X70")
      (libsource (lib "eagle-import") (part "LED25X70"))
    )
    (comp (ref "LED35")
      (value "LED25X70")
      (footprint "eagle-import:LED25X70")
      (libsource (lib "eagle-import") (part "LED25X70"))
    )
    (comp (ref "Q1")
      (value "BS170")
      (footprint "eagle-import:SOT54E")
      (libsource (lib "eagle-import") (part "BS170"))
    )
    (comp (ref "Q2")
      (value "BS170")
      (footprint "eagle-import:SOT54E")
      (libsource (lib "eagle-import") (part "BS170"))
    )
    (comp (ref "Q3")
      (value "BS170")
      (footprint "eagle-import:SOT54E")
      (libsource (lib "eagle-import") (part "BS170"))
    )
    (comp (ref "Q4")
      (value "BS170")
      (footprint "eagle-import:SOT54E")
      (libsource (lib "eagle-import") (part "BS170"))
    )
    (comp (ref "Q5")
      (value "BS170")
      (footprint "eagle-import:SOT54E")
      (libsource (lib "eagle-import") (part "BS170"))
    )
    (comp (ref "Q6")
      (value "BS170")
      (footprint "eagle-import:SOT54E")
      (libsource (lib "eagle-import") (part "BS170"))
    )
    (comp (ref "Q7")
      (value "BS170")
      (footprint "eagle-import:SOT54E")
      (libsource (lib "eagle-import") (part "BS170"))
    )
    (comp (ref "R6")
      (value "200R")
      (footprint "eagle-import:0204_7")
      (libsource (lib "eagle-import") (part "R-EU_0204/7"))
    )
    (comp (ref "R7")
      (value "200R")
      (footprint "eagle-import:0204_7")
      (libsource (lib "eagle-import") (part "R-EU_0204/7"))
    )
    (comp (ref "R8")
      (value "200R")
      (footprint "eagle-import:0204_7")
      (libsource (lib "eagle-import") (part "R-EU_0204/7"))
    )
    (comp (ref "R9")
      (value "200R")
      (footprint "eagle-import:0204_7")
      (libsource (lib "eagle-import") (part "R-EU_0204/7"))
    )
    (comp (ref "R10")
      (value "200R")
      (footprint "eagle-import:0204_7")
      (libsource (lib "eagle-import") (part "R-EU_0204/7"))
    )
    (comp (ref "R11")
      (value "200R")
      (footprint "eagle-import:0204_7")
      (libsource (lib "eagle-import") (part "R-EU_0204/7"))
    )
    (comp (ref "R12")
      (value "200R")
      (footprint "eagle-import:0204_7")
      (libsource (lib "eagle-import") (part "R-EU_0204/7"))
    )
    (comp (ref "R35")
      (value "100K")
      (footprint "eagle-import:0204_7")
      (libsource (lib "eagle-import") (part "R-EU_0204/7"))
    )
    (comp (ref "R36")
      (value "100K")
      (footprint "eagle-import:0204_7")
      (libsource (lib "eagle-import") (part "R-EU_0204/7"))
    )
    (comp (ref "R37")
      (value "100K")
      (footprint "eagle-import:0204_7")
      (libsource (lib "eagle-import") (part "R-EU_0204/7"))
    )
    (comp (ref "R38")
      (value "100K")
      (footprint "eagle-import:0204_7")
      (libsource (lib "eagle-import") (part "R-EU_0204/7"))
    )
    (comp (ref "R39")
      (value "100K")
      (footprint "eagle-import:0204_7")
      (libsource (lib "eagle-import") (part "R-EU_0204/7"))
    )
    (comp (ref "R40")
      (value "100K")
      (footprint "eagle-import:0204_7")
      (libsource (lib "eagle-import") (part "R-EU_0204/7"))
    )
    (comp (ref "R41")
      (value "100K")
      (footprint "eagle-import:0204_7")
      (libsource (lib "eagle-import") (part "R-EU_0204/7"))
    )
    (comp (ref "C3")
      (value "10uF")
      (footprint "eagle-import:E2,5-6")
      (libsource (lib "eagle-import") (part "CPOL-EUE2.5-6"))
    )
    (comp (ref "C4")
      (value "1uF")
      (footprint "eagle-import:C050-024X044")
      (libsource (lib "eagle-import") (part "C-EU050-024X044"))
    )
    (comp (ref "C5")
      (value "100nF")
      (footprint "eagle-import:C050-024X044")
      (libsource (lib "eagle-import") (part "C-EU050-024X044"))
    )
    (comp (ref "C6")
      (value "100nF")
      (footprint "eagle-import:C050-024X044")
      (libsource (lib "eagle-import") (part "C-EU050-024X044"))
    )
    (comp (ref "C7")
      (value "1uF")
      (footprint "eagle-import:C050-024X044")
      (libsource (lib "eagle-import") (part "C-EU050-024X044"))
    )
    (comp (ref "C8")
      (value "100nF")
      (footprint "eagle-import:C050-024X044")
      (libsource (lib "eagle-import") (part "C-EU050-024X044"))
    )
    (comp (ref "C9")
      (value "100nF")
      (footprint "eagle-import:C050-024X044")
      (libsource (lib "eagle-import") (part "C-EU050-024X044"))
    )
    (comp (ref "D1")
      (value "1N5400")
      (footprint "eagle-import:DO201-15")
      (libsource (lib "eagle-import") (part "1N5400"))
    )
    (comp (ref "F1")
      (value "SHK20L")
      (footprint "eagle-import:SHK20L")
      (libsource (lib "eagle-import") (part "SHK20L"))
    )
    (comp (ref "IC1")
      (value "7805L")
      (footprint "eagle-import:TO92")
      (libsource (lib "eagle-import") (part "78L05"))
    )
    (comp (ref "J1")
      (value "JACK-PLUG0")
      (footprint "eagle-import:SPC4077")
      (libsource (lib "eagle-import") (part "JACK-PLUG0"))
    )
    (comp (ref "JP1")
      (value "PINHD-1X6")
      (footprint "eagle-import:1X06")
      (libsource (lib "eagle-import") (part "PINHD-1X6"))
    )
    (comp (ref "PH1")
      (value "A1050_09")
      (footprint "eagle-import:T0-46-A10XX")
      (libsource (lib "eagle-import") (part "A1050_09"))
    )
    (comp (ref "R1")
      (value "5k")
      (footprint "eagle-import:0204_7")
      (libsource (lib "eagle-import") (part "R-EU_0204/7"))
    )
    (comp (ref "R2")
      (value "5k")
      (footprint "eagle-import:0204_7")
      (libsource (lib "eagle-import") (part "R-EU_0204/7"))
    )
    (comp (ref "R3")
      (value "100K")
      (footprint "eagle-import:0204_7")
      (libsource (lib "eagle-import") (part "R-EU_0204/7"))
    )
    (comp (ref "R4")
      (value "5k")
      (footprint "eagle-import:0204_7")
      (libsource (lib "eagle-import") (part "R-EU_0204/7"))
    )
    (comp (ref "R5")
      (value "5k")
      (footprint "eagle-import:0204_7")
      (libsource (lib "eagle-import") (part "R-EU_0204/7"))
    )
    (comp (ref "R64")
      (value "100K")
      (footprint "eagle-import:0204_7")
      (libsource (lib "eagle-import") (part "R-EU_0204/7"))
    )
    (comp (ref "S1")
      (value "DTE6")
      (footprint "eagle-import:DTE6")
      (libsource (lib "eagle-import") (part "DTE6"))
    )
    (comp (ref "S2")
      (value "DTE6")
      (footprint "eagle-import:DTE6")
      (libsource (lib "eagle-import") (part "DTE6"))
    )
    (comp (ref "U1")
      (value "MSP430G2XX3IN20")
      (footprint "eagle-import:DIL20")
      (libsource (lib "eagle-import") (part "MSP430G2XX3IN20"))
    )
    (comp (ref "X1")
      (value "32.768kHz 12.5pF")
      (footprint "eagle-import:TC26H")
      (libsource (lib "eagle-import") (part "CRYSTALTC26H"))
    )
    (comp (ref "C14")
      (value "10uF")
      (footprint "eagle-import:E2,5-6")
      (libsource (lib "eagle-import") (part "CPOL-EUE2.5-6"))
    )
    (comp (ref "C15")
      (value "100nF")
      (footprint "eagle-import:C050-024X044")
      (libsource (lib "eagle-import") (part "C-EU050-024X044"))
    )
    (comp (ref "C16")
      (value "1uF")
      (footprint "eagle-import:C050-024X044")
      (libsource (lib "eagle-import") (part "C-EU050-024X044"))
    )
    (comp (ref "IC4")
      (value "74HC595N")
      (footprint "eagle-import:DIL16")
      (libsource (lib "eagle-import") (part "74595NHC"))
    )
    (comp (ref "LED73")
      (value "LED25X70")
      (footprint "eagle-import:LED25X70")
      (libsource (lib "eagle-import") (part "LED25X70"))
    )
    (comp (ref "LED74")
      (value "LED25X70")
      (footprint "eagle-import:LED25X70")
      (libsource (lib "eagle-import") (part "LED25X70"))
    )
    (comp (ref "LED75")
      (value "LED25X70")
      (footprint "eagle-import:LED25X70")
      (libsource (lib "eagle-import") (part "LED25X70"))
    )
    (comp (ref "LED76")
      (value "LED25X70")
      (footprint "eagle-import:LED25X70")
      (libsource (lib "eagle-import") (part "LED25X70"))
    )
    (comp (ref "LED77")
      (value "LED25X70")
      (footprint "eagle-import:LED25X70")
      (libsource (lib "eagle-import") (part "LED25X70"))
    )
    (comp (ref "LED78")
      (value "LED25X70")
      (footprint "eagle-import:LED25X70")
      (libsource (lib "eagle-import") (part "LED25X70"))
    )
    (comp (ref "LED79")
      (value "LED25X70")
      (footprint "eagle-import:LED25X70")
      (libsource (lib "eagle-import") (part "LED25X70"))
    )
    (comp (ref "LED80")
      (value "LED25X70")
      (footprint "eagle-import:LED25X70")
      (libsource (lib "eagle-import") (part "LED25X70"))
    )
    (comp (ref "LED81")
      (value "LED25X70")
      (footprint "eagle-import:LED25X70")
      (libsource (lib "eagle-import") (part "LED25X70"))
    )
    (comp (ref "LED82")
      (value "LED25X70")
      (footprint "eagle-import:LED25X70")
      (libsource (lib "eagle-import") (part "LED25X70"))
    )
    (comp (ref "LED83")
      (value "LED25X70")
      (footprint "eagle-import:LED25X70")
      (libsource (lib "eagle-import") (part "LED25X70"))
    )
    (comp (ref "LED84")
      (value "LED25X70")
      (footprint "eagle-import:LED25X70")
      (libsource (lib "eagle-import") (part "LED25X70"))
    )
    (comp (ref "LED85")
      (value "LED25X70")
      (footprint "eagle-import:LED25X70")
      (libsource (lib "eagle-import") (part "LED25X70"))
    )
    (comp (ref "LED86")
      (value "LED25X70")
      (footprint "eagle-import:LED25X70")
      (libsource (lib "eagle-import") (part "LED25X70"))
    )
    (comp (ref "LED87")
      (value "LED25X70")
      (footprint "eagle-import:LED25X70")
      (libsource (lib "eagle-import") (part "LED25X70"))
    )
    (comp (ref "LED88")
      (value "LED25X70")
      (footprint "eagle-import:LED25X70")
      (libsource (lib "eagle-import") (part "LED25X70"))
    )
    (comp (ref "LED89")
      (value "LED25X70")
      (footprint "eagle-import:LED25X70")
      (libsource (lib "eagle-import") (part "LED25X70"))
    )
    (comp (ref "LED90")
      (value "LED25X70")
      (footprint "eagle-import:LED25X70")
      (libsource (lib "eagle-import") (part "LED25X70"))
    )
    (comp (ref "LED91")
      (value "LED25X70")
      (footprint "eagle-import:LED25X70")
      (libsource (lib "eagle-import") (part "LED25X70"))
    )
    (comp (ref "LED92")
      (value "LED25X70")
      (footprint "eagle-import:LED25X70")
      (libsource (lib "eagle-import") (part "LED25X70"))
    )
    (comp (ref "LED93")
      (value "LED25X70")
      (footprint "eagle-import:LED25X70")
      (libsource (lib "eagle-import") (part "LED25X70"))
    )
    (comp (ref "LED94")
      (value "LED25X70")
      (footprint "eagle-import:LED25X70")
      (libsource (lib "eagle-import") (part "LED25X70"))
    )
    (comp (ref "LED95")
      (value "LED25X70")
      (footprint "eagle-import:LED25X70")
      (libsource (lib "eagle-import") (part "LED25X70"))
    )
    (comp (ref "LED96")
      (value "LED25X70")
      (footprint "eagle-import:LED25X70")
      (libsource (lib "eagle-import") (part "LED25X70"))
    )
    (comp (ref "LED97")
      (value "LED25X70")
      (footprint "eagle-import:LED25X70")
      (libsource (lib "eagle-import") (part "LED25X70"))
    )
    (comp (ref "LED98")
      (value "LED25X70")
      (footprint "eagle-import:LED25X70")
      (libsource (lib "eagle-import") (part "LED25X70"))
    )
    (comp (ref "LED99")
      (value "LED25X70")
      (footprint "eagle-import:LED25X70")
      (libsource (lib "eagle-import") (part "LED25X70"))
    )
    (comp (ref "LED100")
      (value "LED25X70")
      (footprint "eagle-import:LED25X70")
      (libsource (lib "eagle-import") (part "LED25X70"))
    )
    (comp (ref "LED101")
      (value "LED25X70")
      (footprint "eagle-import:LED25X70")
      (libsource (lib "eagle-import") (part "LED25X70"))
    )
    (comp (ref "LED102")
      (value "LED25X70")
      (footprint "eagle-import:LED25X70")
      (libsource (lib "eagle-import") (part "LED25X70"))
    )
    (comp (ref "LED103")
      (value "LED25X70")
      (footprint "eagle-import:LED25X70")
      (libsource (lib "eagle-import") (part "LED25X70"))
    )
    (comp (ref "LED104")
      (value "LED25X70")
      (footprint "eagle-import:LED25X70")
      (libsource (lib "eagle-import") (part "LED25X70"))
    )
    (comp (ref "LED105")
      (value "LED25X70")
      (footprint "eagle-import:LED25X70")
      (libsource (lib "eagle-import") (part "LED25X70"))
    )
    (comp (ref "LED106")
      (value "LED25X70")
      (footprint "eagle-import:LED25X70")
      (libsource (lib "eagle-import") (part "LED25X70"))
    )
    (comp (ref "LED107")
      (value "LED25X70")
      (footprint "eagle-import:LED25X70")
      (libsource (lib "eagle-import") (part "LED25X70"))
    )
    (comp (ref "Q16")
      (value "BS170")
      (footprint "eagle-import:SOT54E")
      (libsource (lib "eagle-import") (part "BS170"))
    )
    (comp (ref "Q17")
      (value "BS170")
      (footprint "eagle-import:SOT54E")
      (libsource (lib "eagle-import") (part "BS170"))
    )
    (comp (ref "Q18")
      (value "BS170")
      (footprint "eagle-import:SOT54E")
      (libsource (lib "eagle-import") (part "BS170"))
    )
    (comp (ref "Q19")
      (value "BS170")
      (footprint "eagle-import:SOT54E")
      (libsource (lib "eagle-import") (part "BS170"))
    )
    (comp (ref "Q20")
      (value "BS170")
      (footprint "eagle-import:SOT54E")
      (libsource (lib "eagle-import") (part "BS170"))
    )
    (comp (ref "Q21")
      (value "BS170")
      (footprint "eagle-import:SOT54E")
      (libsource (lib "eagle-import") (part "BS170"))
    )
    (comp (ref "Q22")
      (value "BS170")
      (footprint "eagle-import:SOT54E")
      (libsource (lib "eagle-import") (part "BS170"))
    )
    (comp (ref "R21")
      (value "200R")
      (footprint "eagle-import:0204_7")
      (libsource (lib "eagle-import") (part "R-EU_0204/7"))
    )
    (comp (ref "R22")
      (value "200R")
      (footprint "eagle-import:0204_7")
      (libsource (lib "eagle-import") (part "R-EU_0204/7"))
    )
    (comp (ref "R23")
      (value "200R")
      (footprint "eagle-import:0204_7")
      (libsource (lib "eagle-import") (part "R-EU_0204/7"))
    )
    (comp (ref "R24")
      (value "200R")
      (footprint "eagle-import:0204_7")
      (libsource (lib "eagle-import") (part "R-EU_0204/7"))
    )
    (comp (ref "R25")
      (value "200R")
      (footprint "eagle-import:0204_7")
      (libsource (lib "eagle-import") (part "R-EU_0204/7"))
    )
    (comp (ref "R26")
      (value "200R")
      (footprint "eagle-import:0204_7")
      (libsource (lib "eagle-import") (part "R-EU_0204/7"))
    )
    (comp (ref "R27")
      (value "200R")
      (footprint "eagle-import:0204_7")
      (libsource (lib "eagle-import") (part "R-EU_0204/7"))
    )
    (comp (ref "R50")
      (value "100K")
      (footprint "eagle-import:0204_7")
      (libsource (lib "eagle-import") (part "R-EU_0204/7"))
    )
    (comp (ref "R51")
      (value "100K")
      (footprint "eagle-import:0204_7")
      (libsource (lib "eagle-import") (part "R-EU_0204/7"))
    )
    (comp (ref "R52")
      (value "100K")
      (footprint "eagle-import:0204_7")
      (libsource (lib "eagle-import") (part "R-EU_0204/7"))
    )
    (comp (ref "R53")
      (value "100K")
      (footprint "eagle-import:0204_7")
      (libsource (lib "eagle-import") (part "R-EU_0204/7"))
    )
    (comp (ref "R54")
      (value "100K")
      (footprint "eagle-import:0204_7")
      (libsource (lib "eagle-import") (part "R-EU_0204/7"))
    )
    (comp (ref "R55")
      (value "100K")
      (footprint "eagle-import:0204_7")
      (libsource (lib "eagle-import") (part "R-EU_0204/7"))
    )
    (comp (ref "R56")
      (value "100K")
      (footprint "eagle-import:0204_7")
      (libsource (lib "eagle-import") (part "R-EU_0204/7"))
    )
  )
  (nets
    (net (code "1") (name "+3V3") (class "Default")
      (node (ref "C11") (pin "1") (pinfunction "1_1") (pintype "passive"))
      (node (ref "C12") (pin "1") (pinfunction "1_1") (pintype "passive"))
      (node (ref "C13") (pin "1") (pinfunction "1_1") (pintype "passive"))
      (node (ref "C15") (pin "1") (pinfunction "1_1") (pintype "passive"))
      (node (ref "C16") (pin "1") (pinfunction "1_1") (pintype "passive"))
      (node (ref "C18") (pin "1") (pinfunction "1_1") (pintype "passive"))
      (node (ref "C19") (pin "1") (pinfunction "1_1") (pintype "passive"))
      (node (ref "C2") (pin "1") (pinfunction "1_1") (pintype "passive"))
      (node (ref "C5") (pin "1") (pinfunction "1_1") (pintype "passive"))
      (node (ref "C6") (pin "1") (pinfunction "1_1") (pintype "passive"))
      (node (ref "C7") (pin "1") (pinfunction "1_1") (pintype "passive"))
      (node (ref "IC1") (pin "1") (pinfunction "VO_1") (pintype "passive"))
      (node (ref "IC2") (pin "16") (pinfunction "VCC_16") (pintype "power_in"))
      (node (ref "IC3") (pin "16") (pinfunction "VCC_16") (pintype "power_in"))
      (node (ref "IC4") (pin "16") (pinfunction "VCC_16") (pintype "power_in"))
      (node (ref "IC5") (pin "16") (pinfunction "VCC_16") (pintype "power_in"))
      (node (ref "JP1") (pin "1") (pinfunction "1_1") (pintype "passive"))
      (node (ref "PH1") (pin "1") (pinfunction "1_1") (pintype "passive"))
      (node (ref "R1") (pin "2") (pinfunction "2_2") (pintype "passive"))
      (node (ref "R2") (pin "2") (pinfunction "2_2") (pintype "passive"))
      (node (ref "R64") (pin "2") (pinfunction "2_2") (pintype "passive"))
      (node (ref "U1") (pin "1") (pinfunction "VCC_1") (pintype "bidirectional"))
    )
    (net (code "2") (name "+12V") (class "Default")
      (node (ref "C1") (pin "+") (pinfunction "+_+") (pintype "passive"))
      (node (ref "C10") (pin "+") (pinfunction "+_+") (pintype "passive"))
      (node (ref "C14") (pin "+") (pinfunction "+_+") (pintype "passive"))
      (node (ref "C17") (pin "+") (pinfunction "+_+") (pintype "passive"))
      (node (ref "C3") (pin "+") (pinfunction "+_+") (pintype "passive"))
      (node (ref "C4") (pin "1") (pinfunction "1_1") (pintype "passive"))
      (node (ref "D1") (pin "C") (pinfunction "C_C") (pintype "passive"))
      (node (ref "F1") (pin "2A") (pinfunction "2A_2A") (pintype "passive"))
      (node (ref "F1") (pin "2B") (pinfunction "2B_2B") (pintype "passive"))
      (node (ref "IC1") (pin "3") (pinfunction "VI_3") (pintype "input"))
      (node (ref "LED1") (pin "A") (pinfunction "A_A") (pintype "passive"))
      (node (ref "LED103") (pin "A") (pinfunction "A_A") (pintype "passive"))
      (node (ref "LED108") (pin "A") (pinfunction "A_A") (pintype "passive"))
      (node (ref "LED11") (pin "A") (pinfunction "A_A") (pintype "passive"))
      (node (ref "LED113") (pin "A") (pinfunction "A_A") (pintype "passive"))
      (node (ref "LED118") (pin "A") (pinfunction "A_A") (pintype "passive"))
      (node (ref "LED123") (pin "A") (pinfunction "A_A") (pintype "passive"))
      (node (ref "LED128") (pin "A") (pinfunction "A_A") (pintype "passive"))
      (node (ref "LED133") (pin "A") (pinfunction "A_A") (pintype "passive"))
      (node (ref "LED138") (pin "A") (pinfunction "A_A") (pintype "passive"))
      (node (ref "LED16") (pin "A") (pinfunction "A_A") (pintype "passive"))
      (node (ref "LED21") (pin "A") (pinfunction "A_A") (pintype "passive"))
      (node (ref "LED26") (pin "A") (pinfunction "A_A") (pintype "passive"))
      (node (ref "LED31") (pin "A") (pinfunction "A_A") (pintype "passive"))
      (node (ref "LED36") (pin "A") (pinfunction "A_A") (pintype "passive"))
      (node (ref "LED41") (pin "A") (pinfunction "A_A") (pintype "passive"))
      (node (ref "LED46") (pin "A") (pinfunction "A_A") (pintype "passive"))
      (node (ref "LED51") (pin "A") (pinfunction "A_A") (pintype "passive"))
      (node (ref "LED56") (pin "A") (pinfunction "A_A") (pintype "passive"))
      (node (ref "LED6") (pin "A") (pinfunction "A_A") (pintype "passive"))
      (node (ref "LED61") (pin "A") (pinfunction "A_A") (pintype "passive"))
      (node (ref "LED66") (pin "A") (pinfunction "A_A") (pintype "passive"))
      (node (ref "LED71") (pin "A") (pinfunction "A_A") (pintype "passive"))
      (node (ref "LED73") (pin "A") (pinfunction "A_A") (pintype "passive"))
      (node (ref "LED78") (pin "A") (pinfunction "A_A") (pintype "passive"))
      (node (ref "LED83") (pin "A") (pinfunction "A_A") (pintype "passive"))
      (node (ref "LED88") (pin "A") (pinfunction "A_A") (pintype "passive"))
      (node (ref "LED93") (pin "A") (pinfunction "A_A") (pintype "passive"))
      (node (ref "LED98") (pin "A") (pinfunction "A_A") (pintype "passive"))
    )
    (net (code "3") (name "CLR") (class "Default")
      (node (ref "IC2") (pin "10") (pinfunction "SCL_10") (pintype "input"))
      (node (ref "IC3") (pin "10") (pinfunction "SCL_10") (pintype "input"))
      (node (ref "IC4") (pin "10") (pinfunction "SCL_10") (pintype "input"))
      (node (ref "IC5") (pin "10") (pinfunction "SCL_10") (pintype "input"))
      (node (ref "U1") (pin "12") (pinfunction "P2.4_12") (pintype "bidirectional"))
    )
    (net (code "4") (name "DIGIT1_OUT") (class "Default")
      (node (ref "IC2") (pin "9") (pinfunction "QH*_9") (pintype "tri_state"))
      (node (ref "IC3") (pin "14") (pinfunction "SER_14") (pintype "input"))
    )
    (net (code "5") (name "DIGIT2_OUT") (class "Default")
      (node (ref "IC3") (pin "9") (pinfunction "QH*_9") (pintype "tri_state"))
      (node (ref "IC4") (pin "14") (pinfunction "SER_14") (pintype "input"))
    )
    (net (code "6") (name "DIGIT3_OUT") (class "Default")
      (node (ref "IC4") (pin "9") (pinfunction "QH*_9") (pintype "tri_state"))
      (node (ref "IC5") (pin "14") (pinfunction "SER_14") (pintype "input"))
    )
    (net (code "7") (name "ENABLE") (class "Default")
      (node (ref "IC2") (pin "13") (pinfunction "G_13") (pintype "input"))
      (node (ref "IC3") (pin "13") (pinfunction "G_13") (pintype "input"))
      (node (ref "IC4") (pin "13") (pinfunction "G_13") (pintype "input"))
      (node (ref "IC5") (pin "13") (pinfunction "G_13") (pintype "input"))
      (node (ref "U1") (pin "9") (pinfunction "P2.1_9") (pintype "bidirectional"))
    )
    (net (code "8") (name "GND") (class "Default")
      (node (ref "C1") (pin "-") (pinfunction "-_-") (pintype "passive"))
      (node (ref "C10") (pin "-") (pinfunction "-_-") (pintype "passive"))
      (node (ref "C11") (pin "2") (pinfunction "2_2") (pintype "passive"))
      (node (ref "C12") (pin "2") (pinfunction "2_2") (pintype "passive"))
      (node (ref "C13") (pin "2") (pinfunction "2_2") (pintype "passive"))
      (node (ref "C14") (pin "-") (pinfunction "-_-") (pintype "passive"))
      (node (ref "C15") (pin "2") (pinfunction "2_2") (pintype "passive"))
      (node (ref "C16") (pin "2") (pinfunction "2_2") (pintype "passive"))
      (node (ref "C17") (pin "-") (pinfunction "-_-") (pintype "passive"))
      (node (ref "C18") (pin "2") (pinfunction "2_2") (pintype "passive"))
      (node (ref "C19") (pin "2") (pinfunction "2_2") (pintype "passive"))
      (node (ref "C2") (pin "2") (pinfunction "2_2") (pintype "passive"))
      (node (ref "C3") (pin "-") (pinfunction "-_-") (pintype "passive"))
      (node (ref "C4") (pin "2") (pinfunction "2_2") (pintype "passive"))
      (node (ref "C5") (pin "2") (pinfunction "2_2") (pintype "passive"))
      (node (ref "C6") (pin "2") (pinfunction "2_2") (pintype "passive"))
      (node (ref "C7") (pin "2") (pinfunction "2_2") (pintype "passive"))
      (node (ref "C8") (pin "2") (pinfunction "2_2") (pintype "passive"))
      (node (ref "C9") (pin "2") (pinfunction "2_2") (pintype "passive"))
      (node (ref "D1") (pin "A") (pinfunction "A_A") (pintype "passive"))
      (node (ref "IC1") (pin "2") (pinfunction "GND_2") (pintype "passive"))
      (node (ref "IC2") (pin "8") (pinfunction "GND_8") (pintype "power_in"))
      (node (ref "IC3") (pin "8") (pinfunction "GND_8") (pintype "power_in"))
      (node (ref "IC4") (pin "8") (pinfunction "GND_8") (pintype "power_in"))
      (node (ref "IC5") (pin "8") (pinfunction "GND_8") (pintype "power_in"))
      (node (ref "J1") (pin "1") (pinfunction "1_1") (pintype "passive"))
      (node (ref "JP1") (pin "6") (pinfunction "6_6") (pintype "passive"))
      (node (ref "Q1") (pin "S") (pinfunction "S_S") (pintype "passive"))
      (node (ref "Q10") (pin "S") (pinfunction "S_S") (pintype "passive"))
      (node (ref "Q11") (pin "S") (pinfunction "S_S") (pintype "passive"))
      (node (ref "Q12") (pin "S") (pinfunction "S_S") (pintype "passive"))
      (node (ref "Q13") (pin "S") (pinfunction "S_S") (pintype "passive"))
      (node (ref "Q14") (pin "S") (pinfunction "S_S") (pintype "passive"))
      (node (ref "Q15") (pin "S") (pinfunction "S_S") (pintype "passive"))
      (node (ref "Q16") (pin "S") (pinfunction "S_S") (pintype "passive"))
      (node (ref "Q17") (pin "S") (pinfunction "S_S") (pintype "passive"))
      (node (ref "Q18") (pin "S") (pinfunction "S_S") (pintype "passive"))
      (node (ref "Q19") (pin "S") (pinfunction "S_S") (pintype "passive"))
      (node (ref "Q2") (pin "S") (pinfunction "S_S") (pintype "passive"))
      (node (ref "Q20") (pin "S") (pinfunction "S_S") (pintype "passive"))
      (node (ref "Q21") (pin "S") (pinfunction "S_S") (pintype "passive"))
      (node (ref "Q22") (pin "S") (pinfunction "S_S") (pintype "passive"))
      (node (ref "Q23") (pin "S") (pinfunction "S_S") (pintype "passive"))
      (node (ref "Q24") (pin "S") (pinfunction "S_S") (pintype "passive"))
      (node (ref "Q25") (pin "S") (pinfunction "S_S") (pintype "passive"))
      (node (ref "Q26") (pin "S") (pinfunction "S_S") (pintype "passive"))
      (node (ref "Q27") (pin "S") (pinfunction "S_S") (pintype "passive"))
      (node (ref "Q28") (pin "S") (pinfunction "S_S") (pintype "passive"))
      (node (ref "Q29") (pin "S") (pinfunction "S_S") (pintype "passive"))
      (node (ref "Q3") (pin "S") (pinfunction "S_S") (pintype "passive"))
      (node (ref "Q4") (pin "S") (pinfunction "S_S") (pintype "passive"))
      (node (ref "Q5") (pin "S") (pinfunction "S_S") (pintype "passive"))
      (node (ref "Q6") (pin "S") (pinfunction "S_S") (pintype "passive"))
      (node (ref "Q7") (pin "S") (pinfunction "S_S") (pintype "passive"))
      (node (ref "Q8") (pin "S") (pinfunction "S_S") (pintype "passive"))
      (node (ref "Q9") (pin "S") (pinfunction "S_S") (pintype "passive"))
      (node (ref "R3") (pin "1") (pinfunction "1_1") (pintype "passive"))
      (node (ref "R35") (pin "1") (pinfunction "1_1") (pintype "passive"))
      (node (ref "R36") (pin "1") (pinfunction "1_1") (pintype "passive"))
      (node (ref "R37") (pin "1") (pinfunction "1_1") (pintype "passive"))
      (node (ref "R38") (pin "1") (pinfunction "1_1") (pintype "passive"))
      (node (ref "R39") (pin "1") (pinfunction "1_1") (pintype "passive"))
      (node (ref "R40") (pin "1") (pinfunction "1_1") (pintype "passive"))
      (node (ref "R41") (pin "1") (pinfunction "1_1") (pintype "passive"))
      (node (ref "R42") (pin "1") (pinfunction "1_1") (pintype "passive"))
      (node (ref "R43") (pin "1") (pinfunction "1_1") (pintype "passive"))
      (node (ref "R44") (pin "1") (pinfunction "1_1") (pintype "passive"))
      (node (ref "R45") (pin "1") (pinfunction "1_1") (pintype "passive"))
      (node (ref "R46") (pin "1") (pinfunction "1_1") (pintype "passive"))
      (node (ref "R47") (pin "1") (pinfunction "1_1") (pintype "passive"))
      (node (ref "R48") (pin "1") (pinfunction "1_1") (pintype "passive"))
      (node (ref "R49") (pin "1") (pinfunction "1_1") (pintype "passive"))
      (node (ref "R50") (pin "1") (pinfunction "1_1") (pintype "passive"))
      (node (ref "R51") (pin "1") (pinfunction "1_1") (pintype "passive"))
      (node (ref "R52") (pin "1") (pinfunction "1_1") (pintype "passive"))
      (node (ref "R53") (pin "1") (pinfunction "1_1") (pintype "passive"))
      (node (ref "R54") (pin "1") (pinfunction "1_1") (pintype "passive"))
      (node (ref "R55") (pin "1") (pinfunction "1_1") (pintype "passive"))
      (node (ref "R56") (pin "1") (pinfunction "1_1") (pintype "passive"))
      (node (ref "R57") (pin "1") (pinfunction "1_1") (pintype "passive"))
      (node (ref "R58") (pin "1") (pinfunction "1_1") (pintype "passive"))
      (node (ref "R59") (pin "1") (pinfunction "1_1") (pintype "passive"))
      (node (ref "R60") (pin "1") (pinfunction "1_1") (pintype "passive"))
      (node (ref "R61") (pin "1") (pinfunction "1_1") (pintype "passive"))
      (node (ref "R62") (pin "1") (pinfunction "1_1") (pintype "passive"))
      (node (ref "R63") (pin "1") (pinfunction "1_1") (pintype "passive"))
      (node (ref "S1") (pin "3") (pinfunction "P_3") (pintype "passive"))
      (node (ref "S1") (pin "4") (pinfunction "P_4") (pintype "passive"))
      (node (ref "S2") (pin "1") (pinfunction "S_1") (pintype "passive"))
      (node (ref "S2") (pin "2") (pinfunction "S_2") (pintype "passive"))
      (node (ref "U1") (pin "20") (pinfunction "GND_20") (pintype "bidirectional"))
    )
    (net (code "9") (name "LIGHT") (class "Default")
      (node (ref "PH1") (pin "2") (pinfunction "2_2") (pintype "passive"))
      (node (ref "R3") (pin "2") (pinfunction "2_2") (pintype "passive"))
      (node (ref "U1") (pin "6") (pinfunction "P1.4_6") (pintype "bidirectional"))
    )
    (net (code "10") (name "Net-(F1-Pad1A)") (class "Default")
      (node (ref "F1") (pin "1A") (pinfunction "1A_1A") (pintype "passive"))
      (node (ref "F1") (pin "1B") (pinfunction "1B_1B") (pintype "passive"))
      (node (ref "J1") (pin "3") (pinfunction "3_3") (pintype "passive"))
    )
    (net (code "11") (name "Net-(IC2A-QA)") (class "Default")
      (node (ref "IC2") (pin "15") (pinfunction "QA_15") (pintype "tri_state"))
      (node (ref "Q1") (pin "G") (pinfunction "G_G") (pintype "passive"))
      (node (ref "R35") (pin "2") (pinfunction "2_2") (pintype "passive"))
    )
    (net (code "12") (name "Net-(IC2A-QB)") (class "Default")
      (node (ref "IC2") (pin "1") (pinfunction "QB_1") (pintype "tri_state"))
      (node (ref "Q2") (pin "G") (pinfunction "G_G") (pintype "passive"))
      (node (ref "R36") (pin "2") (pinfunction "2_2") (pintype "passive"))
    )
    (net (code "13") (name "Net-(IC2A-QC)") (class "Default")
      (node (ref "IC2") (pin "2") (pinfunction "QC_2") (pintype "tri_state"))
      (node (ref "Q3") (pin "G") (pinfunction "G_G") (pintype "passive"))
      (node (ref "R37") (pin "2") (pinfunction "2_2") (pintype "passive"))
    )
    (net (code "14") (name "Net-(IC2A-QD)") (class "Default")
      (node (ref "IC2") (pin "3") (pinfunction "QD_3") (pintype "tri_state"))
      (node (ref "Q4") (pin "G") (pinfunction "G_G") (pintype "passive"))
      (node (ref "R38") (pin "2") (pinfunction "2_2") (pintype "passive"))
    )
    (net (code "15") (name "Net-(IC2A-QE)") (class "Default")
      (node (ref "IC2") (pin "4") (pinfunction "QE_4") (pintype "tri_state"))
      (node (ref "Q5") (pin "G") (pinfunction "G_G") (pintype "passive"))
      (node (ref "R39") (pin "2") (pinfunction "2_2") (pintype "passive"))
    )
    (net (code "16") (name "Net-(IC2A-QF)") (class "Default")
      (node (ref "IC2") (pin "5") (pinfunction "QF_5") (pintype "tri_state"))
      (node (ref "Q6") (pin "G") (pinfunction "G_G") (pintype "passive"))
      (node (ref "R40") (pin "2") (pinfunction "2_2") (pintype "passive"))
    )
    (net (code "17") (name "Net-(IC2A-QG)") (class "Default")
      (node (ref "IC2") (pin "6") (pinfunction "QG_6") (pintype "tri_state"))
      (node (ref "Q7") (pin "G") (pinfunction "G_G") (pintype "passive"))
      (node (ref "R41") (pin "2") (pinfunction "2_2") (pintype "passive"))
    )
    (net (code "18") (name "Net-(IC3A-QA)") (class "Default")
      (node (ref "IC3") (pin "15") (pinfunction "QA_15") (pintype "tri_state"))
      (node (ref "Q8") (pin "G") (pinfunction "G_G") (pintype "passive"))
      (node (ref "R42") (pin "2") (pinfunction "2_2") (pintype "passive"))
    )
    (net (code "19") (name "Net-(IC3A-QB)") (class "Default")
      (node (ref "IC3") (pin "1") (pinfunction "QB_1") (pintype "tri_state"))
      (node (ref "Q9") (pin "G") (pinfunction "G_G") (pintype "passive"))
      (node (ref "R43") (pin "2") (pinfunction "2_2") (pintype "passive"))
    )
    (net (code "20") (name "Net-(IC3A-QC)") (class "Default")
      (node (ref "IC3") (pin "2") (pinfunction "QC_2") (pintype "tri_state"))
      (node (ref "Q10") (pin "G") (pinfunction "G_G") (pintype "passive"))
      (node (ref "R44") (pin "2") (pinfunction "2_2") (pintype "passive"))
    )
    (net (code "21") (name "Net-(IC3A-QD)") (class "Default")
      (node (ref "IC3") (pin "3") (pinfunction "QD_3") (pintype "tri_state"))
      (node (ref "Q11") (pin "G") (pinfunction "G_G") (pintype "passive"))
      (node (ref "R45") (pin "2") (pinfunction "2_2") (pintype "passive"))
    )
    (net (code "22") (name "Net-(IC3A-QE)") (class "Default")
      (node (ref "IC3") (pin "4") (pinfunction "QE_4") (pintype "tri_state"))
      (node (ref "Q12") (pin "G") (pinfunction "G_G") (pintype "passive"))
      (node (ref "R46") (pin "2") (pinfunction "2_2") (pintype "passive"))
    )
    (net (code "23") (name "Net-(IC3A-QF)") (class "Default")
      (node (ref "IC3") (pin "5") (pinfunction "QF_5") (pintype "tri_state"))
      (node (ref "Q13") (pin "G") (pinfunction "G_G") (pintype "passive"))
      (node (ref "R47") (pin "2") (pinfunction "2_2") (pintype "passive"))
    )
    (net (code "24") (name "Net-(IC3A-QG)") (class "Default")
      (node (ref "IC3") (pin "6") (pinfunction "QG_6") (pintype "tri_state"))
      (node (ref "Q14") (pin "G") (pinfunction "G_G") (pintype "passive"))
      (node (ref "R48") (pin "2") (pinfunction "2_2") (pintype "passive"))
    )
    (net (code "25") (name "Net-(IC3A-QH)") (class "Default")
      (node (ref "IC3") (pin "7") (pinfunction "QH_7") (pintype "tri_state"))
      (node (ref "Q15") (pin "G") (pinfunction "G_G") (pintype "passive"))
      (node (ref "R49") (pin "2") (pinfunction "2_2") (pintype "passive"))
    )
    (net (code "26") (name "Net-(IC4A-QA)") (class "Default")
      (node (ref "IC4") (pin "15") (pinfunction "QA_15") (pintype "tri_state"))
      (node (ref "Q16") (pin "G") (pinfunction "G_G") (pintype "passive"))
      (node (ref "R50") (pin "2") (pinfunction "2_2") (pintype "passive"))
    )
    (net (code "27") (name "Net-(IC4A-QB)") (class "Default")
      (node (ref "IC4") (pin "1") (pinfunction "QB_1") (pintype "tri_state"))
      (node (ref "Q17") (pin "G") (pinfunction "G_G") (pintype "passive"))
      (node (ref "R51") (pin "2") (pinfunction "2_2") (pintype "passive"))
    )
    (net (code "28") (name "Net-(IC4A-QC)") (class "Default")
      (node (ref "IC4") (pin "2") (pinfunction "QC_2") (pintype "tri_state"))
      (node (ref "Q18") (pin "G") (pinfunction "G_G") (pintype "passive"))
      (node (ref "R52") (pin "2") (pinfunction "2_2") (pintype "passive"))
    )
    (net (code "29") (name "Net-(IC4A-QD)") (class "Default")
      (node (ref "IC4") (pin "3") (pinfunction "QD_3") (pintype "tri_state"))
      (node (ref "Q19") (pin "G") (pinfunction "G_G") (pintype "passive"))
      (node (ref "R53") (pin "2") (pinfunction "2_2") (pintype "passive"))
    )
    (net (code "30") (name "Net-(IC4A-QE)") (class "Default")
      (node (ref "IC4") (pin "4") (pinfunction "QE_4") (pintype "tri_state"))
      (node (ref "Q20") (pin "G") (pinfunction "G_G") (pintype "passive"))
      (node (ref "R54") (pin "2") (pinfunction "2_2") (pintype "passive"))
    )
    (net (code "31") (name "Net-(IC4A-QF)") (class "Default")
      (node (ref "IC4") (pin "5") (pinfunction "QF_5") (pintype "tri_state"))
      (node (ref "Q21") (pin "G") (pinfunction "G_G") (pintype "passive"))
      (node (ref "R55") (pin "2") (pinfunction "2_2") (pintype "passive"))
    )
    (net (code "32") (name "Net-(IC4A-QG)") (class "Default")
      (node (ref "IC4") (pin "6") (pinfunction "QG_6") (pintype "tri_state"))
      (node (ref "Q22") (pin "G") (pinfunction "G_G") (pintype "passive"))
      (node (ref "R56") (pin "2") (pinfunction "2_2") (pintype "passive"))
    )
    (net (code "33") (name "Net-(IC5A-QA)") (class "Default")
      (node (ref "IC5") (pin "15") (pinfunction "QA_15") (pintype "tri_state"))
      (node (ref "Q23") (pin "G") (pinfunction "G_G") (pintype "passive"))
      (node (ref "R57") (pin "2") (pinfunction "2_2") (pintype "passive"))
    )
    (net (code "34") (name "Net-(IC5A-QB)") (class "Default")
      (node (ref "IC5") (pin "1") (pinfunction "QB_1") (pintype "tri_state"))
      (node (ref "Q24") (pin "G") (pinfunction "G_G") (pintype "passive"))
      (node (ref "R58") (pin "2") (pinfunction "2_2") (pintype "passive"))
    )
    (net (code "35") (name "Net-(IC5A-QC)") (class "Default")
      (node (ref "IC5") (pin "2") (pinfunction "QC_2") (pintype "tri_state"))
      (node (ref "Q25") (pin "G") (pinfunction "G_G") (pintype "passive"))
      (node (ref "R59") (pin "2") (pinfunction "2_2") (pintype "passive"))
    )
    (net (code "36") (name "Net-(IC5A-QD)") (class "Default")
      (node (ref "IC5") (pin "3") (pinfunction "QD_3") (pintype "tri_state"))
      (node (ref "Q26") (pin "G") (pinfunction "G_G") (pintype "passive"))
      (node (ref "R60") (pin "2") (pinfunction "2_2") (pintype "passive"))
    )
    (net (code "37") (name "Net-(IC5A-QE)") (class "Default")
      (node (ref "IC5") (pin "4") (pinfunction "QE_4") (pintype "tri_state"))
      (node (ref "Q27") (pin "G") (pinfunction "G_G") (pintype "passive"))
      (node (ref "R61") (pin "2") (pinfunction "2_2") (pintype "passive"))
    )
    (net (code "38") (name "Net-(IC5A-QF)") (class "Default")
      (node (ref "IC5") (pin "5") (pinfunction "QF_5") (pintype "tri_state"))
      (node (ref "Q28") (pin "G") (pinfunction "G_G") (pintype "passive"))
      (node (ref "R62") (pin "2") (pinfunction "2_2") (pintype "passive"))
    )
    (net (code "39") (name "Net-(IC5A-QG)") (class "Default")
      (node (ref "IC5") (pin "6") (pinfunction "QG_6") (pintype "tri_state"))
      (node (ref "Q29") (pin "G") (pinfunction "G_G") (pintype "passive"))
      (node (ref "R63") (pin "2") (pinfunction "2_2") (pintype "passive"))
    )
    (net (code "40") (name "Net-(LED1-C)") (class "Default")
      (node (ref "LED1") (pin "K") (pinfunction "C_K") (pintype "passive"))
      (node (ref "LED2") (pin "A") (pinfunction "A_A") (pintype "passive"))
    )
    (net (code "41") (name "Net-(LED2-C)") (class "Default")
      (node (ref "LED2") (pin "K") (pinfunction "C_K") (pintype "passive"))
      (node (ref "LED3") (pin "A") (pinfunction "A_A") (pintype "passive"))
    )
    (net (code "42") (name "Net-(LED3-C)") (class "Default")
      (node (ref "LED3") (pin "K") (pinfunction "C_K") (pintype "passive"))
      (node (ref "LED4") (pin "A") (pinfunction "A_A") (pintype "passive"))
    )
    (net (code "43") (name "Net-(LED4-C)") (class "Default")
      (node (ref "LED4") (pin "K") (pinfunction "C_K") (pintype "passive"))
      (node (ref "LED5") (pin "A") (pinfunction "A_A") (pintype "passive"))
    )
    (net (code "44") (name "Net-(LED5-C)") (class "Default")
      (node (ref "LED5") (pin "K") (pinfunction "C_K") (pintype "passive"))
      (node (ref "R6") (pin "2") (pinfunction "2_2") (pintype "passive"))
    )
    (net (code "45") (name "Net-(LED6-C)") (class "Default")
      (node (ref "LED6") (pin "K") (pinfunction "C_K") (pintype "passive"))
      (node (ref "LED7") (pin "A") (pinfunction "A_A") (pintype "passive"))
    )
    (net (code "46") (name "Net-(LED7-C)") (class "Default")
      (node (ref "LED7") (pin "K") (pinfunction "C_K") (pintype "passive"))
      (node (ref "LED8") (pin "A") (pinfunction "A_A") (pintype "passive"))
    )
    (net (code "47") (name "Net-(LED8-C)") (class "Default")
      (node (ref "LED8") (pin "K") (pinfunction "C_K") (pintype "passive"))
      (node (ref "LED9") (pin "A") (pinfunction "A_A") (pintype "passive"))
    )
    (net (code "48") (name "Net-(LED9-C)") (class "Default")
      (node (ref "LED10") (pin "A") (pinfunction "A_A") (pintype "passive"))
      (node (ref "LED9") (pin "K") (pinfunction "C_K") (pintype "passive"))
    )
    (net (code "49") (name "Net-(LED10-C)") (class "Default")
      (node (ref "LED10") (pin "K") (pinfunction "C_K") (pintype "passive"))
      (node (ref "R7") (pin "2") (pinfunction "2_2") (pintype "passive"))
    )
    (net (code "50") (name "Net-(LED11-C)") (class "Default")
      (node (ref "LED11") (pin "K") (pinfunction "C_K") (pintype "passive"))
      (node (ref "LED12") (pin "A") (pinfunction "A_A") (pintype "passive"))
    )
    (net (code "51") (name "Net-(LED12-C)") (class "Default")
      (node (ref "LED12") (pin "K") (pinfunction "C_K") (pintype "passive"))
      (node (ref "LED13") (pin "A") (pinfunction "A_A") (pintype "passive"))
    )
    (net (code "52") (name "Net-(LED13-C)") (class "Default")
      (node (ref "LED13") (pin "K") (pinfunction "C_K") (pintype "passive"))
      (node (ref "LED14") (pin "A") (pinfunction "A_A") (pintype "passive"))
    )
    (net (code "53") (name "Net-(LED14-C)") (class "Default")
      (node (ref "LED14") (pin "K") (pinfunction "C_K") (pintype "passive"))
      (node (ref "LED15") (pin "A") (pinfunction "A_A") (pintype "passive"))
    )
    (net (code "54") (name "Net-(LED15-C)") (class "Default")
      (node (ref "LED15") (pin "K") (pinfunction "C_K") (pintype "passive"))
      (node (ref "R8") (pin "2") (pinfunction "2_2") (pintype "passive"))
    )
    (net (code "55") (name "Net-(LED16-C)") (class "Default")
      (node (ref "LED16") (pin "K") (pinfunction "C_K") (pintype "passive"))
      (node (ref "LED17") (pin "A") (pinfunction "A_A") (pintype "passive"))
    )
    (net (code "56") (name "Net-(LED17-C)") (class "Default")
      (node (ref "LED17") (pin "K") (pinfunction "C_K") (pintype "passive"))
      (node (ref "LED18") (pin "A") (pinfunction "A_A") (pintype "passive"))
    )
    (net (code "57") (name "Net-(LED18-C)") (class "Default")
      (node (ref "LED18") (pin "K") (pinfunction "C_K") (pintype "passive"))
      (node (ref "LED19") (pin "A") (pinfunction "A_A") (pintype "passive"))
    )
    (net (code "58") (name "Net-(LED19-C)") (class "Default")
      (node (ref "LED19") (pin "K") (pinfunction "C_K") (pintype "passive"))
      (node (ref "LED20") (pin "A") (pinfunction "A_A") (pintype "passive"))
    )
    (net (code "59") (name "Net-(LED20-C)") (class "Default")
      (node (ref "LED20") (pin "K") (pinfunction "C_K") (pintype "passive"))
      (node (ref "R9") (pin "2") (pinfunction "2_2") (pintype "passive"))
    )
    (net (code "60") (name "Net-(LED21-C)") (class "Default")
      (node (ref "LED21") (pin "K") (pinfunction "C_K") (pintype "passive"))
      (node (ref "LED22") (pin "A") (pinfunction "A_A") (pintype "passive"))
    )
    (net (code "61") (name "Net-(LED22-C)") (class "Default")
      (node (ref "LED22") (pin "K") (pinfunction "C_K") (pintype "passive"))
      (node (ref "LED23") (pin "A") (pinfunction "A_A") (pintype "passive"))
    )
    (net (code "62") (name "Net-(LED23-C)") (class "Default")
      (node (ref "LED23") (pin "K") (pinfunction "C_K") (pintype "passive"))
      (node (ref "LED24") (pin "A") (pinfunction "A_A") (pintype "passive"))
    )
    (net (code "63") (name "Net-(LED24-C)") (class "Default")
      (node (ref "LED24") (pin "K") (pinfunction "C_K") (pintype "passive"))
      (node (ref "LED25") (pin "A") (pinfunction "A_A") (pintype "passive"))
    )
    (net (code "64") (name "Net-(LED25-C)") (class "Default")
      (node (ref "LED25") (pin "K") (pinfunction "C_K") (pintype "passive"))
      (node (ref "R10") (pin "2") (pinfunction "2_2") (pintype "passive"))
    )
    (net (code "65") (name "Net-(LED26-C)") (class "Default")
      (node (ref "LED26") (pin "K") (pinfunction "C_K") (pintype "passive"))
      (node (ref "LED27") (pin "A") (pinfunction "A_A") (pintype "passive"))
    )
    (net (code "66") (name "Net-(LED27-C)") (class "Default")
      (node (ref "LED27") (pin "K") (pinfunction "C_K") (pintype "passive"))
      (node (ref "LED28") (pin "A") (pinfunction "A_A") (pintype "passive"))
    )
    (net (code "67") (name "Net-(LED28-C)") (class "Default")
      (node (ref "LED28") (pin "K") (pinfunction "C_K") (pintype "passive"))
      (node (ref "LED29") (pin "A") (pinfunction "A_A") (pintype "passive"))
    )
    (net (code "68") (name "Net-(LED29-C)") (class "Default")
      (node (ref "LED29") (pin "K") (pinfunction "C_K") (pintype "passive"))
      (node (ref "LED30") (pin "A") (pinfunction "A_A") (pintype "passive"))
    )
    (net (code "69") (name "Net-(LED30-C)") (class "Default")
      (node (ref "LED30") (pin "K") (pinfunction "C_K") (pintype "passive"))
      (node (ref "R11") (pin "2") (pinfunction "2_2") (pintype "passive"))
    )
    (net (code "70") (name "Net-(LED31-C)") (class "Default")
      (node (ref "LED31") (pin "K") (pinfunction "C_K") (pintype "passive"))
      (node (ref "LED32") (pin "A") (pinfunction "A_A") (pintype "passive"))
    )
    (net (code "71") (name "Net-(LED32-C)") (class "Default")
      (node (ref "LED32") (pin "K") (pinfunction "C_K") (pintype "passive"))
      (node (ref "LED33") (pin "A") (pinfunction "A_A") (pintype "passive"))
    )
    (net (code "72") (name "Net-(LED33-C)") (class "Default")
      (node (ref "LED33") (pin "K") (pinfunction "C_K") (pintype "passive"))
      (node (ref "LED34") (pin "A") (pinfunction "A_A") (pintype "passive"))
    )
    (net (code "73") (name "Net-(LED34-C)") (class "Default")
      (node (ref "LED34") (pin "K") (pinfunction "C_K") (pintype "passive"))
      (node (ref "LED35") (pin "A") (pinfunction "A_A") (pintype "passive"))
    )
    (net (code "74") (name "Net-(LED35-C)") (class "Default")
      (node (ref "LED35") (pin "K") (pinfunction "C_K") (pintype "passive"))
      (node (ref "R12") (pin "2") (pinfunction "2_2") (pintype "passive"))
    )
    (net (code "75") (name "Net-(LED36-C)") (class "Default")
      (node (ref "LED36") (pin "K") (pinfunction "C_K") (pintype "passive"))
      (node (ref "LED37") (pin "A") (pinfunction "A_A") (pintype "passive"))
    )
    (net (code "76") (name "Net-(LED37-C)") (class "Default")
      (node (ref "LED37") (pin "K") (pinfunction "C_K") (pintype "passive"))
      (node (ref "LED38") (pin "A") (pinfunction "A_A") (pintype "passive"))
    )
    (net (code "77") (name "Net-(LED38-C)") (class "Default")
      (node (ref "LED38") (pin "K") (pinfunction "C_K") (pintype "passive"))
      (node (ref "LED39") (pin "A") (pinfunction "A_A") (pintype "passive"))
    )
    (net (code "78") (name "Net-(LED39-C)") (class "Default")
      (node (ref "LED39") (pin "K") (pinfunction "C_K") (pintype "passive"))
      (node (ref "LED40") (pin "A") (pinfunction "A_A") (pintype "passive"))
    )
    (net (code "79") (name "Net-(LED40-C)") (class "Default")
      (node (ref "LED40") (pin "K") (pinfunction "C_K") (pintype "passive"))
      (node (ref "R13") (pin "2") (pinfunction "2_2") (pintype "passive"))
    )
    (net (code "80") (name "Net-(LED41-C)") (class "Default")
      (node (ref "LED41") (pin "K") (pinfunction "C_K") (pintype "passive"))
      (node (ref "LED42") (pin "A") (pinfunction "A_A") (pintype "passive"))
    )
    (net (code "81") (name "Net-(LED42-C)") (class "Default")
      (node (ref "LED42") (pin "K") (pinfunction "C_K") (pintype "passive"))
      (node (ref "LED43") (pin "A") (pinfunction "A_A") (pintype "passive"))
    )
    (net (code "82") (name "Net-(LED43-C)") (class "Default")
      (node (ref "LED43") (pin "K") (pinfunction "C_K") (pintype "passive"))
      (node (ref "LED44") (pin "A") (pinfunction "A_A") (pintype "passive"))
    )
    (net (code "83") (name "Net-(LED44-C)") (class "Default")
      (node (ref "LED44") (pin "K") (pinfunction "C_K") (pintype "passive"))
      (node (ref "LED45") (pin "A") (pinfunction "A_A") (pintype "passive"))
    )
    (net (code "84") (name "Net-(LED45-C)") (class "Default")
      (node (ref "LED45") (pin "K") (pinfunction "C_K") (pintype "passive"))
      (node (ref "R14") (pin "2") (pinfunction "2_2") (pintype "passive"))
    )
    (net (code "85") (name "Net-(LED46-C)") (class "Default")
      (node (ref "LED46") (pin "K") (pinfunction "C_K") (pintype "passive"))
      (node (ref "LED47") (pin "A") (pinfunction "A_A") (pintype "passive"))
    )
    (net (code "86") (name "Net-(LED47-C)") (class "Default")
      (node (ref "LED47") (pin "K") (pinfunction "C_K") (pintype "passive"))
      (node (ref "LED48") (pin "A") (pinfunction "A_A") (pintype "passive"))
    )
    (net (code "87") (name "Net-(LED48-C)") (class "Default")
      (node (ref "LED48") (pin "K") (pinfunction "C_K") (pintype "passive"))
      (node (ref "LED49") (pin "A") (pinfunction "A_A") (pintype "passive"))
    )
    (net (code "88") (name "Net-(LED49-C)") (class "Default")
      (node (ref "LED49") (pin "K") (pinfunction "C_K") (pintype "passive"))
      (node (ref "LED50") (pin "A") (pinfunction "A_A") (pintype "passive"))
    )
    (net (code "89") (name "Net-(LED50-C)") (class "Default")
      (node (ref "LED50") (pin "K") (pinfunction "C_K") (pintype "passive"))
      (node (ref "R15") (pin "2") (pinfunction "2_2") (pintype "passive"))
    )
    (net (code "90") (name "Net-(LED51-C)") (class "Default")
      (node (ref "LED51") (pin "K") (pinfunction "C_K") (pintype "passive"))
      (node (ref "LED52") (pin "A") (pinfunction "A_A") (pintype "passive"))
    )
    (net (code "91") (name "Net-(LED52-C)") (class "Default")
      (node (ref "LED52") (pin "K") (pinfunction "C_K") (pintype "passive"))
      (node (ref "LED53") (pin "A") (pinfunction "A_A") (pintype "passive"))
    )
    (net (code "92") (name "Net-(LED53-C)") (class "Default")
      (node (ref "LED53") (pin "K") (pinfunction "C_K") (pintype "passive"))
      (node (ref "LED54") (pin "A") (pinfunction "A_A") (pintype "passive"))
    )
    (net (code "93") (name "Net-(LED54-C)") (class "Default")
      (node (ref "LED54") (pin "K") (pinfunction "C_K") (pintype "passive"))
      (node (ref "LED55") (pin "A") (pinfunction "A_A") (pintype "passive"))
    )
    (net (code "94") (name "Net-(LED55-C)") (class "Default")
      (node (ref "LED55") (pin "K") (pinfunction "C_K") (pintype "passive"))
      (node (ref "R16") (pin "2") (pinfunction "2_2") (pintype "passive"))
    )
    (net (code "95") (name "Net-(LED56-C)") (class "Default")
      (node (ref "LED56") (pin "K") (pinfunction "C_K") (pintype "passive"))
      (node (ref "LED57") (pin "A") (pinfunction "A_A") (pintype "passive"))
    )
    (net (code "96") (name "Net-(LED57-C)") (class "Default")
      (node (ref "LED57") (pin "K") (pinfunction "C_K") (pintype "passive"))
      (node (ref "LED58") (pin "A") (pinfunction "A_A") (pintype "passive"))
    )
    (net (code "97") (name "Net-(LED58-C)") (class "Default")
      (node (ref "LED58") (pin "K") (pinfunction "C_K") (pintype "passive"))
      (node (ref "LED59") (pin "A") (pinfunction "A_A") (pintype "passive"))
    )
    (net (code "98") (name "Net-(LED59-C)") (class "Default")
      (node (ref "LED59") (pin "K") (pinfunction "C_K") (pintype "passive"))
      (node (ref "LED60") (pin "A") (pinfunction "A_A") (pintype "passive"))
    )
    (net (code "99") (name "Net-(LED60-C)") (class "Default")
      (node (ref "LED60") (pin "K") (pinfunction "C_K") (pintype "passive"))
      (node (ref "R17") (pin "2") (pinfunction "2_2") (pintype "passive"))
    )
    (net (code "100") (name "Net-(LED61-C)") (class "Default")
      (node (ref "LED61") (pin "K") (pinfunction "C_K") (pintype "passive"))
      (node (ref "LED62") (pin "A") (pinfunction "A_A") (pintype "passive"))
    )
    (net (code "101") (name "Net-(LED62-C)") (class "Default")
      (node (ref "LED62") (pin "K") (pinfunction "C_K") (pintype "passive"))
      (node (ref "LED63") (pin "A") (pinfunction "A_A") (pintype "passive"))
    )
    (net (code "102") (name "Net-(LED63-C)") (class "Default")
      (node (ref "LED63") (pin "K") (pinfunction "C_K") (pintype "passive"))
      (node (ref "LED64") (pin "A") (pinfunction "A_A") (pintype "passive"))
    )
    (net (code "103") (name "Net-(LED64-C)") (class "Default")
      (node (ref "LED64") (pin "K") (pinfunction "C_K") (pintype "passive"))
      (node (ref "LED65") (pin "A") (pinfunction "A_A") (pintype "passive"))
    )
    (net (code "104") (name "Net-(LED65-C)") (class "Default")
      (node (ref "LED65") (pin "K") (pinfunction "C_K") (pintype "passive"))
      (node (ref "R18") (pin "2") (pinfunction "2_2") (pintype "passive"))
    )
    (net (code "105") (name "Net-(LED66-C)") (class "Default")
      (node (ref "LED66") (pin "K") (pinfunction "C_K") (pintype "passive"))
      (node (ref "LED67") (pin "A") (pinfunction "A_A") (pintype "passive"))
    )
    (net (code "106") (name "Net-(LED67-C)") (class "Default")
      (node (ref "LED67") (pin "K") (pinfunction "C_K") (pintype "passive"))
      (node (ref "LED68") (pin "A") (pinfunction "A_A") (pintype "passive"))
    )
    (net (code "107") (name "Net-(LED68-C)") (class "Default")
      (node (ref "LED68") (pin "K") (pinfunction "C_K") (pintype "passive"))
      (node (ref "LED69") (pin "A") (pinfunction "A_A") (pintype "passive"))
    )
    (net (code "108") (name "Net-(LED69-C)") (class "Default")
      (node (ref "LED69") (pin "K") (pinfunction "C_K") (pintype "passive"))
      (node (ref "LED70") (pin "A") (pinfunction "A_A") (pintype "passive"))
    )
    (net (code "109") (name "Net-(LED70-C)") (class "Default")
      (node (ref "LED70") (pin "K") (pinfunction "C_K") (pintype "passive"))
      (node (ref "R19") (pin "2") (pinfunction "2_2") (pintype "passive"))
    )
    (net (code "110") (name "Net-(LED71-C)") (class "Default")
      (node (ref "LED71") (pin "K") (pinfunction "C_K") (pintype "passive"))
      (node (ref "LED72") (pin "A") (pinfunction "A_A") (pintype "passive"))
    )
    (net (code "111") (name "Net-(LED72-C)") (class "Default")
      (node (ref "LED72") (pin "K") (pinfunction "C_K") (pintype "passive"))
      (node (ref "R20") (pin "2") (pinfunction "2_2") (pintype "passive"))
    )
    (net (code "112") (name "Net-(LED73-C)") (class "Default")
      (node (ref "LED73") (pin "K") (pinfunction "C_K") (pintype "passive"))
      (node (ref "LED74") (pin "A") (pinfunction "A_A") (pintype "passive"))
    )
    (net (code "113") (name "Net-(LED74-C)") (class "Default")
      (node (ref "LED74") (pin "K") (pinfunction "C_K") (pintype "passive"))
      (node (ref "LED75") (pin "A") (pinfunction "A_A") (pintype "passive"))
    )
    (net (code "114") (name "Net-(LED75-C)") (class "Default")
      (node (ref "LED75") (pin "K") (pinfunction "C_K") (pintype "passive"))
      (node (ref "LED76") (pin "A") (pinfunction "A_A") (pintype "passive"))
    )
    (net (code "115") (name "Net-(LED76-C)") (class "Default")
      (node (ref "LED76") (pin "K") (pinfunction "C_K") (pintype "passive"))
      (node (ref "LED77") (pin "A") (pinfunction "A_A") (pintype "passive"))
    )
    (net (code "116") (name "Net-(LED77-C)") (class "Default")
      (node (ref "LED77") (pin "K") (pinfunction "C_K") (pintype "passive"))
      (node (ref "R21") (pin "2") (pinfunction "2_2") (pintype "passive"))
    )
    (net (code "117") (name "Net-(LED78-C)") (class "Default")
      (node (ref "LED78") (pin "K") (pinfunction "C_K") (pintype "passive"))
      (node (ref "LED79") (pin "A") (pinfunction "A_A") (pintype "passive"))
    )
    (net (code "118") (name "Net-(LED79-C)") (class "Default")
      (node (ref "LED79") (pin "K") (pinfunction "C_K") (pintype "passive"))
      (node (ref "LED80") (pin "A") (pinfunction "A_A") (pintype "passive"))
    )
    (net (code "119") (name "Net-(LED80-C)") (class "Default")
      (node (ref "LED80") (pin "K") (pinfunction "C_K") (pintype "passive"))
      (node (ref "LED81") (pin "A") (pinfunction "A_A") (pintype "passive"))
    )
    (net (code "120") (name "Net-(LED81-C)") (class "Default")
      (node (ref "LED81") (pin "K") (pinfunction "C_K") (pintype "passive"))
      (node (ref "LED82") (pin "A") (pinfunction "A_A") (pintype "passive"))
    )
    (net (code "121") (name "Net-(LED82-C)") (class "Default")
      (node (ref "LED82") (pin "K") (pinfunction "C_K") (pintype "passive"))
      (node (ref "R22") (pin "2") (pinfunction "2_2") (pintype "passive"))
    )
    (net (code "122") (name "Net-(LED83-C)") (class "Default")
      (node (ref "LED83") (pin "K") (pinfunction "C_K") (pintype "passive"))
      (node (ref "LED84") (pin "A") (pinfunction "A_A") (pintype "passive"))
    )
    (net (code "123") (name "Net-(LED84-C)") (class "Default")
      (node (ref "LED84") (pin "K") (pinfunction "C_K") (pintype "passive"))
      (node (ref "LED85") (pin "A") (pinfunction "A_A") (pintype "passive"))
    )
    (net (code "124") (name "Net-(LED85-C)") (class "Default")
      (node (ref "LED85") (pin "K") (pinfunction "C_K") (pintype "passive"))
      (node (ref "LED86") (pin "A") (pinfunction "A_A") (pintype "passive"))
    )
    (net (code "125") (name "Net-(LED86-C)") (class "Default")
      (node (ref "LED86") (pin "K") (pinfunction "C_K") (pintype "passive"))
      (node (ref "LED87") (pin "A") (pinfunction "A_A") (pintype "passive"))
    )
    (net (code "126") (name "Net-(LED87-C)") (class "Default")
      (node (ref "LED87") (pin "K") (pinfunction "C_K") (pintype "passive"))
      (node (ref "R23") (pin "2") (pinfunction "2_2") (pintype "passive"))
    )
    (net (code "127") (name "Net-(LED88-C)") (class "Default")
      (node (ref "LED88") (pin "K") (pinfunction "C_K") (pintype "passive"))
      (node (ref "LED89") (pin "A") (pinfunction "A_A") (pintype "passive"))
    )
    (net (code "128") (name "Net-(LED89-C)") (class "Default")
      (node (ref "LED89") (pin "K") (pinfunction "C_K") (pintype "passive"))
      (node (ref "LED90") (pin "A") (pinfunction "A_A") (pintype "passive"))
    )
    (net (code "129") (name "Net-(LED90-C)") (class "Default")
      (node (ref "LED90") (pin "K") (pinfunction "C_K") (pintype "passive"))
      (node (ref "LED91") (pin "A") (pinfunction "A_A") (pintype "passive"))
    )
    (net (code "130") (name "Net-(LED91-C)") (class "Default")
      (node (ref "LED91") (pin "K") (pinfunction "C_K") (pintype "passive"))
      (node (ref "LED92") (pin "A") (pinfunction "A_A") (pintype "passive"))
    )
    (net (code "131") (name "Net-(LED92-C)") (class "Default")
      (node (ref "LED92") (pin "K") (pinfunction "C_K") (pintype "passive"))
      (node (ref "R24") (pin "2") (pinfunction "2_2") (pintype "passive"))
    )
    (net (code "132") (name "Net-(LED93-C)") (class "Default")
      (node (ref "LED93") (pin "K") (pinfunction "C_K") (pintype "passive"))
      (node (ref "LED94") (pin "A") (pinfunction "A_A") (pintype "passive"))
    )
    (net (code "133") (name "Net-(LED94-C)") (class "Default")
      (node (ref "LED94") (pin "K") (pinfunction "C_K") (pintype "passive"))
      (node (ref "LED95") (pin "A") (pinfunction "A_A") (pintype "passive"))
    )
    (net (code "134") (name "Net-(LED95-C)") (class "Default")
      (node (ref "LED95") (pin "K") (pinfunction "C_K") (pintype "passive"))
      (node (ref "LED96") (pin "A") (pinfunction "A_A") (pintype "passive"))
    )
    (net (code "135") (name "Net-(LED96-C)") (class "Default")
      (node (ref "LED96") (pin "K") (pinfunction "C_K") (pintype "passive"))
      (node (ref "LED97") (pin "A") (pinfunction "A_A") (pintype "passive"))
    )
    (net (code "136") (name "Net-(LED97-C)") (class "Default")
      (node (ref "LED97") (pin "K") (pinfunction "C_K") (pintype "passive"))
      (node (ref "R25") (pin "2") (pinfunction "2_2") (pintype "passive"))
    )
    (net (code "137") (name "Net-(LED98-C)") (class "Default")
      (node (ref "LED98") (pin "K") (pinfunction "C_K") (pintype "passive"))
      (node (ref "LED99") (pin "A") (pinfunction "A_A") (pintype "passive"))
    )
    (net (code "138") (name "Net-(LED99-C)") (class "Default")
      (node (ref "LED100") (pin "A") (pinfunction "A_A") (pintype "passive"))
      (node (ref "LED99") (pin "K") (pinfunction "C_K") (pintype "passive"))
    )
    (net (code "139") (name "Net-(LED100-C)") (class "Default")
      (node (ref "LED100") (pin "K") (pinfunction "C_K") (pintype "passive"))
      (node (ref "LED101") (pin "A") (pinfunction "A_A") (pintype "passive"))
    )
    (net (code "140") (name "Net-(LED101-C)") (class "Default")
      (node (ref "LED101") (pin "K") (pinfunction "C_K") (pintype "passive"))
      (node (ref "LED102") (pin "A") (pinfunction "A_A") (pintype "passive"))
    )
    (net (code "141") (name "Net-(LED102-C)") (class "Default")
      (node (ref "LED102") (pin "K") (pinfunction "C_K") (pintype "passive"))
      (node (ref "R26") (pin "2") (pinfunction "2_2") (pintype "passive"))
    )
    (net (code "142") (name "Net-(LED103-C)") (class "Default")
      (node (ref "LED103") (pin "K") (pinfunction "C_K") (pintype "passive"))
      (node (ref "LED104") (pin "A") (pinfunction "A_A") (pintype "passive"))
    )
    (net (code "143") (name "Net-(LED104-C)") (class "Default")
      (node (ref "LED104") (pin "K") (pinfunction "C_K") (pintype "passive"))
      (node (ref "LED105") (pin "A") (pinfunction "A_A") (pintype "passive"))
    )
    (net (code "144") (name "Net-(LED105-C)") (class "Default")
      (node (ref "LED105") (pin "K") (pinfunction "C_K") (pintype "passive"))
      (node (ref "LED106") (pin "A") (pinfunction "A_A") (pintype "passive"))
    )
    (net (code "145") (name "Net-(LED106-C)") (class "Default")
      (node (ref "LED106") (pin "K") (pinfunction "C_K") (pintype "passive"))
      (node (ref "LED107") (pin "A") (pinfunction "A_A") (pintype "passive"))
    )
    (net (code "146") (name "Net-(LED107-C)") (class "Default")
      (node (ref "LED107") (pin "K") (pinfunction "C_K") (pintype "passive"))
      (node (ref "R27") (pin "2") (pinfunction "2_2") (pintype "passive"))
    )
    (net (code "147") (name "Net-(LED108-C)") (class "Default")
      (node (ref "LED108") (pin "K") (pinfunction "C_K") (pintype "passive"))
      (node (ref "LED109") (pin "A") (pinfunction "A_A") (pintype "passive"))
    )
    (net (code "148") (name "Net-(LED109-C)") (class "Default")
      (node (ref "LED109") (pin "K") (pinfunction "C_K") (pintype "passive"))
      (node (ref "LED110") (pin "A") (pinfunction "A_A") (pintype "passive"))
    )
    (net (code "149") (name "Net-(LED110-C)") (class "Default")
      (node (ref "LED110") (pin "K") (pinfunction "C_K") (pintype "passive"))
      (node (ref "LED111") (pin "A") (pinfunction "A_A") (pintype "passive"))
    )
    (net (code "150") (name "Net-(LED111-C)") (class "Default")
      (node (ref "LED111") (pin "K") (pinfunction "C_K") (pintype "passive"))
      (node (ref "LED112") (pin "A") (pinfunction "A_A") (pintype "passive"))
    )
    (net (code "151") (name "Net-(LED112-C)") (class "Default")
      (node (ref "LED112") (pin "K") (pinfunction "C_K") (pintype "passive"))
      (node (ref "R28") (pin "2") (pinfunction "2_2") (pintype "passive"))
    )
    (net (code "152") (name "Net-(LED113-C)") (class "Default")
      (node (ref "LED113") (pin "K") (pinfunction "C_K") (pintype "passive"))
      (node (ref "LED114") (pin "A") (pinfunction "A_A") (pintype "passive"))
    )
    (net (code "153") (name "Net-(LED114-C)") (class "Default")
      (node (ref "LED114") (pin "K") (pinfunction "C_K") (pintype "passive"))
      (node (ref "LED115") (pin "A") (pinfunction "A_A") (pintype "passive"))
    )
    (net (code "154") (name "Net-(LED115-C)") (class "Default")
      (node (ref "LED115") (pin "K") (pinfunction "C_K") (pintype "passive"))
      (node (ref "LED116") (pin "A") (pinfunction "A_A") (pintype "passive"))
    )
    (net (code "155") (name "Net-(LED116-C)") (class "Default")
      (node (ref "LED116") (pin "K") (pinfunction "C_K") (pintype "passive"))
      (node (ref "LED117") (pin "A") (pinfunction "A_A") (pintype "passive"))
    )
    (net (code "156") (name "Net-(LED117-C)") (class "Default")
      (node (ref "LED117") (pin "K") (pinfunction "C_K") (pintype "passive"))
      (node (ref "R29") (pin "2") (pinfunction "2_2") (pintype "passive"))
    )
    (net (code "157") (name "Net-(LED118-C)") (class "Default")
      (node (ref "LED118") (pin "K") (pinfunction "C_K") (pintype "passive"))
      (node (ref "LED119") (pin "A") (pinfunction "A_A") (pintype "passive"))
    )
    (net (code "158") (name "Net-(LED119-C)") (class "Default")
      (node (ref "LED119") (pin "K") (pinfunction "C_K") (pintype "passive"))
      (node (ref "LED120") (pin "A") (pinfunction "A_A") (pintype "passive"))
    )
    (net (code "159") (name "Net-(LED120-C)") (class "Default")
      (node (ref "LED120") (pin "K") (pinfunction "C_K") (pintype "passive"))
      (node (ref "LED121") (pin "A") (pinfunction "A_A") (pintype "passive"))
    )
    (net (code "160") (name "Net-(LED121-C)") (class "Default")
      (node (ref "LED121") (pin "K") (pinfunction "C_K") (pintype "passive"))
      (node (ref "LED122") (pin "A") (pinfunction "A_A") (pintype "passive"))
    )
    (net (code "161") (name "Net-(LED122-C)") (class "Default")
      (node (ref "LED122") (pin "K") (pinfunction "C_K") (pintype "passive"))
      (node (ref "R30") (pin "2") (pinfunction "2_2") (pintype "passive"))
    )
    (net (code "162") (name "Net-(LED123-C)") (class "Default")
      (node (ref "LED123") (pin "K") (pinfunction "C_K") (pintype "passive"))
      (node (ref "LED124") (pin "A") (pinfunction "A_A") (pintype "passive"))
    )
    (net (code "163") (name "Net-(LED124-C)") (class "Default")
      (node (ref "LED124") (pin "K") (pinfunction "C_K") (pintype "passive"))
      (node (ref "LED125") (pin "A") (pinfunction "A_A") (pintype "passive"))
    )
    (net (code "164") (name "Net-(LED125-C)") (class "Default")
      (node (ref "LED125") (pin "K") (pinfunction "C_K") (pintype "passive"))
      (node (ref "LED126") (pin "A") (pinfunction "A_A") (pintype "passive"))
    )
    (net (code "165") (name "Net-(LED126-C)") (class "Default")
      (node (ref "LED126") (pin "K") (pinfunction "C_K") (pintype "passive"))
      (node (ref "LED127") (pin "A") (pinfunction "A_A") (pintype "passive"))
    )
    (net (code "166") (name "Net-(LED127-C)") (class "Default")
      (node (ref "LED127") (pin "K") (pinfunction "C_K") (pintype "passive"))
      (node (ref "R31") (pin "2") (pinfunction "2_2") (pintype "passive"))
    )
    (net (code "167") (name "Net-(LED128-C)") (class "Default")
      (node (ref "LED128") (pin "K") (pinfunction "C_K") (pintype "passive"))
      (node (ref "LED129") (pin "A") (pinfunction "A_A") (pintype "passive"))
    )
    (net (code "168") (name "Net-(LED129-C)") (class "Default")
      (node (ref "LED129") (pin "K") (pinfunction "C_K") (pintype "passive"))
      (node (ref "LED130") (pin "A") (pinfunction "A_A") (pintype "passive"))
    )
    (net (code "169") (name "Net-(LED130-C)") (class "Default")
      (node (ref "LED130") (pin "K") (pinfunction "C_K") (pintype "passive"))
      (node (ref "LED131") (pin "A") (pinfunction "A_A") (pintype "passive"))
    )
    (net (code "170") (name "Net-(LED131-C)") (class "Default")
      (node (ref "LED131") (pin "K") (pinfunction "C_K") (pintype "passive"))
      (node (ref "LED132") (pin "A") (pinfunction "A_A") (pintype "passive"))
    )
    (net (code "171") (name "Net-(LED132-C)") (class "Default")
      (node (ref "LED132") (pin "K") (pinfunction "C_K") (pintype "passive"))
      (node (ref "R32") (pin "2") (pinfunction "2_2") (pintype "passive"))
    )
    (net (code "172") (name "Net-(LED133-C)") (class "Default")
      (node (ref "LED133") (pin "K") (pinfunction "C_K") (pintype "passive"))
      (node (ref "LED134") (pin "A") (pinfunction "A_A") (pintype "passive"))
    )
    (net (code "173") (name "Net-(LED134-C)") (class "Default")
      (node (ref "LED134") (pin "K") (pinfunction "C_K") (pintype "passive"))
      (node (ref "LED135") (pin "A") (pinfunction "A_A") (pintype "passive"))
    )
    (net (code "174") (name "Net-(LED135-C)") (class "Default")
      (node (ref "LED135") (pin "K") (pinfunction "C_K") (pintype "passive"))
      (node (ref "LED136") (pin "A") (pinfunction "A_A") (pintype "passive"))
    )
    (net (code "175") (name "Net-(LED136-C)") (class "Default")
      (node (ref "LED136") (pin "K") (pinfunction "C_K") (pintype "passive"))
      (node (ref "LED137") (pin "A") (pinfunction "A_A") (pintype "passive"))
    )
    (net (code "176") (name "Net-(LED137-C)") (class "Default")
      (node (ref "LED137") (pin "K") (pinfunction "C_K") (pintype "passive"))
      (node (ref "R33") (pin "2") (pinfunction "2_2") (pintype "passive"))
    )
    (net (code "177") (name "Net-(LED138-C)") (class "Default")
      (node (ref "LED138") (pin "K") (pinfunction "C_K") (pintype "passive"))
      (node (ref "LED139") (pin "A") (pinfunction "A_A") (pintype "passive"))
    )
    (net (code "178") (name "Net-(LED139-C)") (class "Default")
      (node (ref "LED139") (pin "K") (pinfunction "C_K") (pintype "passive"))
      (node (ref "LED140") (pin "A") (pinfunction "A_A") (pintype "passive"))
    )
    (net (code "179") (name "Net-(LED140-C)") (class "Default")
      (node (ref "LED140") (pin "K") (pinfunction "C_K") (pintype "passive"))
      (node (ref "LED141") (pin "A") (pinfunction "A_A") (pintype "passive"))
    )
    (net (code "180") (name "Net-(LED141-C)") (class "Default")
      (node (ref "LED141") (pin "K") (pinfunction "C_K") (pintype "passive"))
      (node (ref "LED142") (pin "A") (pinfunction "A_A") (pintype "passive"))
    )
    (net (code "181") (name "Net-(LED142-C)") (class "Default")
      (node (ref "LED142") (pin "K") (pinfunction "C_K") (pintype "passive"))
      (node (ref "R34") (pin "2") (pinfunction "2_2") (pintype "passive"))
    )
    (net (code "182") (name "Net-(Q1-PadD)") (class "Default")
      (node (ref "Q1") (pin "D") (pinfunction "D_D") (pintype "passive"))
      (node (ref "R6") (pin "1") (pinfunction "1_1") (pintype "passive"))
    )
    (net (code "183") (name "Net-(Q2-PadD)") (class "Default")
      (node (ref "Q2") (pin "D") (pinfunction "D_D") (pintype "passive"))
      (node (ref "R7") (pin "1") (pinfunction "1_1") (pintype "passive"))
    )
    (net (code "184") (name "Net-(Q3-PadD)") (class "Default")
      (node (ref "Q3") (pin "D") (pinfunction "D_D") (pintype "passive"))
      (node (ref "R8") (pin "1") (pinfunction "1_1") (pintype "passive"))
    )
    (net (code "185") (name "Net-(Q4-PadD)") (class "Default")
      (node (ref "Q4") (pin "D") (pinfunction "D_D") (pintype "passive"))
      (node (ref "R9") (pin "1") (pinfunction "1_1") (pintype "passive"))
    )
    (net (code "186") (name "Net-(Q5-PadD)") (class "Default")
      (node (ref "Q5") (pin "D") (pinfunction "D_D") (pintype "passive"))
      (node (ref "R10") (pin "1") (pinfunction "1_1") (pintype "passive"))
    )
    (net (code "187") (name "Net-(Q6-PadD)") (class "Default")
      (node (ref "Q6") (pin "D") (pinfunction "D_D") (pintype "passive"))
      (node (ref "R11") (pin "1") (pinfunction "1_1") (pintype "passive"))
    )
    (net (code "188") (name "Net-(Q7-PadD)") (class "Default")
      (node (ref "Q7") (pin "D") (pinfunction "D_D") (pintype "passive"))
      (node (ref "R12") (pin "1") (pinfunction "1_1") (pintype "passive"))
    )
    (net (code "189") (name "Net-(Q8-PadD)") (class "Default")
      (node (ref "Q8") (pin "D") (pinfunction "D_D") (pintype "passive"))
      (node (ref "R13") (pin "1") (pinfunction "1_1") (pintype "passive"))
    )
    (net (code "190") (name "Net-(Q9-PadD)") (class "Default")
      (node (ref "Q9") (pin "D") (pinfunction "D_D") (pintype "passive"))
      (node (ref "R14") (pin "1") (pinfunction "1_1") (pintype "passive"))
    )
    (net (code "191") (name "Net-(Q10-PadD)") (class "Default")
      (node (ref "Q10") (pin "D") (pinfunction "D_D") (pintype "passive"))
      (node (ref "R15") (pin "1") (pinfunction "1_1") (pintype "passive"))
    )
    (net (code "192") (name "Net-(Q11-PadD)") (class "Default")
      (node (ref "Q11") (pin "D") (pinfunction "D_D") (pintype "passive"))
      (node (ref "R16") (pin "1") (pinfunction "1_1") (pintype "passive"))
    )
    (net (code "193") (name "Net-(Q12-PadD)") (class "Default")
      (node (ref "Q12") (pin "D") (pinfunction "D_D") (pintype "passive"))
      (node (ref "R17") (pin "1") (pinfunction "1_1") (pintype "passive"))
    )
    (net (code "194") (name "Net-(Q13-PadD)") (class "Default")
      (node (ref "Q13") (pin "D") (pinfunction "D_D") (pintype "passive"))
      (node (ref "R18") (pin "1") (pinfunction "1_1") (pintype "passive"))
    )
    (net (code "195") (name "Net-(Q14-PadD)") (class "Default")
      (node (ref "Q14") (pin "D") (pinfunction "D_D") (pintype "passive"))
      (node (ref "R19") (pin "1") (pinfunction "1_1") (pintype "passive"))
    )
    (net (code "196") (name "Net-(Q15-PadD)") (class "Default")
      (node (ref "Q15") (pin "D") (pinfunction "D_D") (pintype "passive"))
      (node (ref "R20") (pin "1") (pinfunction "1_1") (pintype "passive"))
    )
    (net (code "197") (name "Net-(Q16-PadD)") (class "Default")
      (node (ref "Q16") (pin "D") (pinfunction "D_D") (pintype "passive"))
      (node (ref "R21") (pin "1") (pinfunction "1_1") (pintype "passive"))
    )
    (net (code "198") (name "Net-(Q17-PadD)") (class "Default")
      (node (ref "Q17") (pin "D") (pinfunction "D_D") (pintype "passive"))
      (node (ref "R22") (pin "1") (pinfunction "1_1") (pintype "passive"))
    )
    (net (code "199") (name "Net-(Q18-PadD)") (class "Default")
      (node (ref "Q18") (pin "D") (pinfunction "D_D") (pintype "passive"))
      (node (ref "R23") (pin "1") (pinfunction "1_1") (pintype "passive"))
    )
    (net (code "200") (name "Net-(Q19-PadD)") (class "Default")
      (node (ref "Q19") (pin "D") (pinfunction "D_D") (pintype "passive"))
      (node (ref "R24") (pin "1") (pinfunction "1_1") (pintype "passive"))
    )
    (net (code "201") (name "Net-(Q20-PadD)") (class "Default")
      (node (ref "Q20") (pin "D") (pinfunction "D_D") (pintype "passive"))
      (node (ref "R25") (pin "1") (pinfunction "1_1") (pintype "passive"))
    )
    (net (code "202") (name "Net-(Q21-PadD)") (class "Default")
      (node (ref "Q21") (pin "D") (pinfunction "D_D") (pintype "passive"))
      (node (ref "R26") (pin "1") (pinfunction "1_1") (pintype "passive"))
    )
    (net (code "203") (name "Net-(Q22-PadD)") (class "Default")
      (node (ref "Q22") (pin "D") (pinfunction "D_D") (pintype "passive"))
      (node (ref "R27") (pin "1") (pinfunction "1_1") (pintype "passive"))
    )
    (net (code "204") (name "Net-(Q23-PadD)") (class "Default")
      (node (ref "Q23") (pin "D") (pinfunction "D_D") (pintype "passive"))
      (node (ref "R28") (pin "1") (pinfunction "1_1") (pintype "passive"))
    )
    (net (code "205") (name "Net-(Q24-PadD)") (class "Default")
      (node (ref "Q24") (pin "D") (pinfunction "D_D") (pintype "passive"))
      (node (ref "R29") (pin "1") (pinfunction "1_1") (pintype "passive"))
    )
    (net (code "206") (name "Net-(Q25-PadD)") (class "Default")
      (node (ref "Q25") (pin "D") (pinfunction "D_D") (pintype "passive"))
      (node (ref "R30") (pin "1") (pinfunction "1_1") (pintype "passive"))
    )
    (net (code "207") (name "Net-(Q26-PadD)") (class "Default")
      (node (ref "Q26") (pin "D") (pinfunction "D_D") (pintype "passive"))
      (node (ref "R31") (pin "1") (pinfunction "1_1") (pintype "passive"))
    )
    (net (code "208") (name "Net-(Q27-PadD)") (class "Default")
      (node (ref "Q27") (pin "D") (pinfunction "D_D") (pintype "passive"))
      (node (ref "R32") (pin "1") (pinfunction "1_1") (pintype "passive"))
    )
    (net (code "209") (name "Net-(Q28-PadD)") (class "Default")
      (node (ref "Q28") (pin "D") (pinfunction "D_D") (pintype "passive"))
      (node (ref "R33") (pin "1") (pinfunction "1_1") (pintype "passive"))
    )
    (net (code "210") (name "Net-(Q29-PadD)") (class "Default")
      (node (ref "Q29") (pin "D") (pinfunction "D_D") (pintype "passive"))
      (node (ref "R34") (pin "1") (pinfunction "1_1") (pintype "passive"))
    )
    (net (code "211") (name "Net-(R1-Pad1)") (class "Default")
      (node (ref "R1") (pin "1") (pinfunction "1_1") (pintype "passive"))
      (node (ref "R5") (pin "2") (pinfunction "2_2") (pintype "passive"))
      (node (ref "S1") (pin "1") (pinfunction "S_1") (pintype "passive"))
      (node (ref "S1") (pin "2") (pinfunction "S_2") (pintype "passive"))
    )
    (net (code "212") (name "Net-(R2-Pad1)") (class "Default")
      (node (ref "R2") (pin "1") (pinfunction "1_1") (pintype "passive"))
      (node (ref "R4") (pin "2") (pinfunction "2_2") (pintype "passive"))
      (node (ref "S2") (pin "3") (pinfunction "P_3") (pintype "passive"))
      (node (ref "S2") (pin "4") (pinfunction "P_4") (pintype "passive"))
    )
    (net (code "213") (name "RCK") (class "Default")
      (node (ref "IC2") (pin "12") (pinfunction "RCK_12") (pintype "input"))
      (node (ref "IC3") (pin "12") (pinfunction "RCK_12") (pintype "input"))
      (node (ref "IC4") (pin "12") (pinfunction "RCK_12") (pintype "input"))
      (node (ref "IC5") (pin "12") (pinfunction "RCK_12") (pintype "input"))
      (node (ref "U1") (pin "11") (pinfunction "P2.3_11") (pintype "bidirectional"))
    )
    (net (code "214") (name "RFU@2") (class "Default")
      (node (ref "U1") (pin "2") (pinfunction "P1.0_2") (pintype "bidirectional"))
    )
    (net (code "215") (name "RFU@7") (class "Default")
      (node (ref "U1") (pin "7") (pinfunction "P1.5_7") (pintype "bidirectional"))
    )
    (net (code "216") (name "RFU@14") (class "Default")
      (node (ref "U1") (pin "14") (pinfunction "P1.6_14") (pintype "bidirectional"))
    )
    (net (code "217") (name "RFU@15") (class "Default")
      (node (ref "U1") (pin "15") (pinfunction "P1.7_15") (pintype "bidirectional"))
    )
    (net (code "218") (name "RX") (class "Default")
      (node (ref "JP1") (pin "4") (pinfunction "4_4") (pintype "passive"))
      (node (ref "U1") (pin "3") (pinfunction "P1.1_3") (pintype "bidirectional"))
    )
    (net (code "219") (name "SCK") (class "Default")
      (node (ref "IC2") (pin "11") (pinfunction "SCK_11") (pintype "input"))
      (node (ref "IC3") (pin "11") (pinfunction "SCK_11") (pintype "input"))
      (node (ref "IC4") (pin "11") (pinfunction "SCK_11") (pintype "input"))
      (node (ref "IC5") (pin "11") (pinfunction "SCK_11") (pintype "input"))
      (node (ref "U1") (pin "8") (pinfunction "P2.0_8") (pintype "bidirectional"))
    )
    (net (code "220") (name "SER") (class "Default")
      (node (ref "IC2") (pin "14") (pinfunction "SER_14") (pintype "input"))
      (node (ref "U1") (pin "10") (pinfunction "P2.2_10") (pintype "bidirectional"))
    )
    (net (code "221") (name "SW1") (class "Default")
      (node (ref "C9") (pin "1") (pinfunction "1_1") (pintype "passive"))
      (node (ref "R5") (pin "1") (pinfunction "1_1") (pintype "passive"))
      (node (ref "U1") (pin "5") (pinfunction "P1.3_5") (pintype "bidirectional"))
    )
    (net (code "222") (name "SW2") (class "Default")
      (node (ref "C8") (pin "1") (pinfunction "1_1") (pintype "passive"))
      (node (ref "R4") (pin "1") (pinfunction "1_1") (pintype "passive"))
      (node (ref "U1") (pin "13") (pinfunction "P2.5_13") (pintype "bidirectional"))
    )
    (net (code "223") (name "SWCLK") (class "Default")
      (node (ref "JP1") (pin "3") (pinfunction "3_3") (pintype "passive"))
      (node (ref "U1") (pin "17") (pinfunction "SBWTCK_17") (pintype "bidirectional"))
    )
    (net (code "224") (name "SWDIO") (class "Default")
      (node (ref "JP1") (pin "2") (pinfunction "2_2") (pintype "passive"))
      (node (ref "R64") (pin "1") (pinfunction "1_1") (pintype "passive"))
      (node (ref "U1") (pin "16") (pinfunction "NRST/SBWTDIO_16") (pintype "bidirectional"))
    )
    (net (code "225") (name "TX") (class "Default")
      (node (ref "JP1") (pin "5") (pinfunction "5_5") (pintype "passive"))
      (node (ref "U1") (pin "4") (pinfunction "P1.2_4") (pintype "bidirectional"))
    )
    (net (code "226") (name "XIN") (class "Default")
      (node (ref "U1") (pin "18") (pinfunction "P2.6/XIN_18") (pintype "bidirectional"))
      (node (ref "X1") (pin "2") (pinfunction "2_2") (pintype "passive"))
    )
    (net (code "227") (name "XOUT") (class "Default")
      (node (ref "U1") (pin "19") (pinfunction "P2.7/XOUT_19") (pintype "bidirectional"))
      (node (ref "X1") (pin "1") (pinfunction "1_1") (pintype "passive"))
    )
    (net (code "228") (name "unconnected-(IC2A-QH-Pad7)") (class "Default")
      (node (ref "IC2") (pin "7") (pinfunction "QH_7") (pintype "tri_state"))
    )
    (net (code "229") (name "unconnected-(IC4A-QH-Pad7)") (class "Default")
      (node (ref "IC4") (pin "7") (pinfunction "QH_7") (pintype "tri_state"))
    )
    (net (code "230") (name "unconnected-(IC5A-QH*-Pad9)") (class "Default")
      (node (ref "IC5") (pin "9") (pinfunction "QH*_9") (pintype "tri_state"))
    )
    (net (code "231") (name "unconnected-(IC5A-QH-Pad7)") (class "Default")
      (node (ref "IC5") (pin "7") (pinfunction "QH_7") (pintype "tri_state"))
    )
    (net (code "232") (name "unconnected-(J1-Pad2)") (class "Default")
      (node (ref "J1") (pin "2") (pinfunction "2_2") (pintype "passive"))
    )
  )
)
